# demo_V1_SMALL_SIZE.net
KiCad netlist of a schematic drawn in Altium Designer
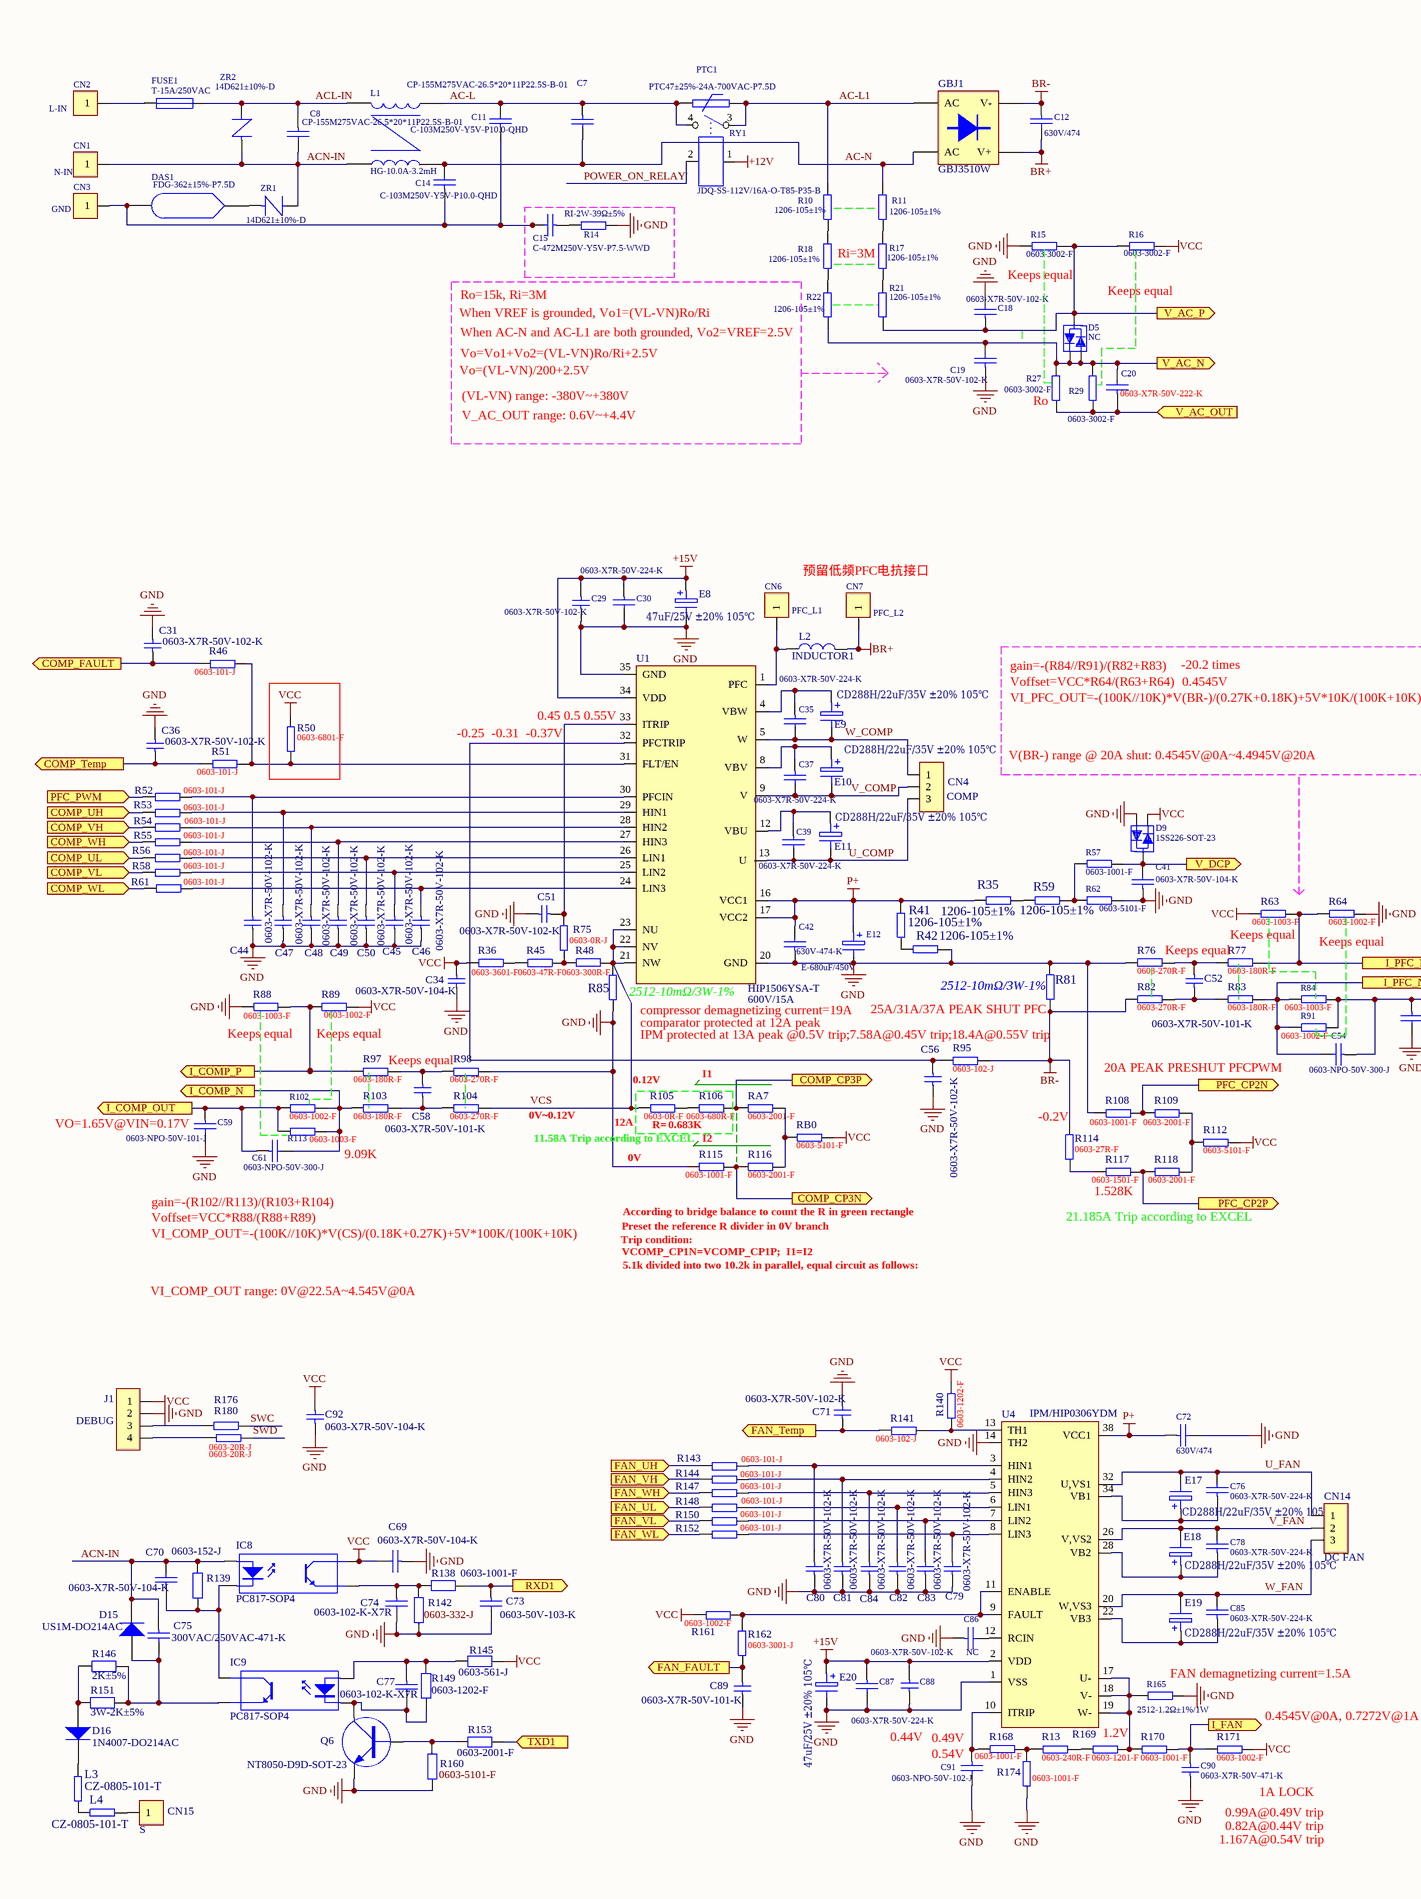
[diagram p0: demo_V1 SMALL SIZE.SchDoc, left]
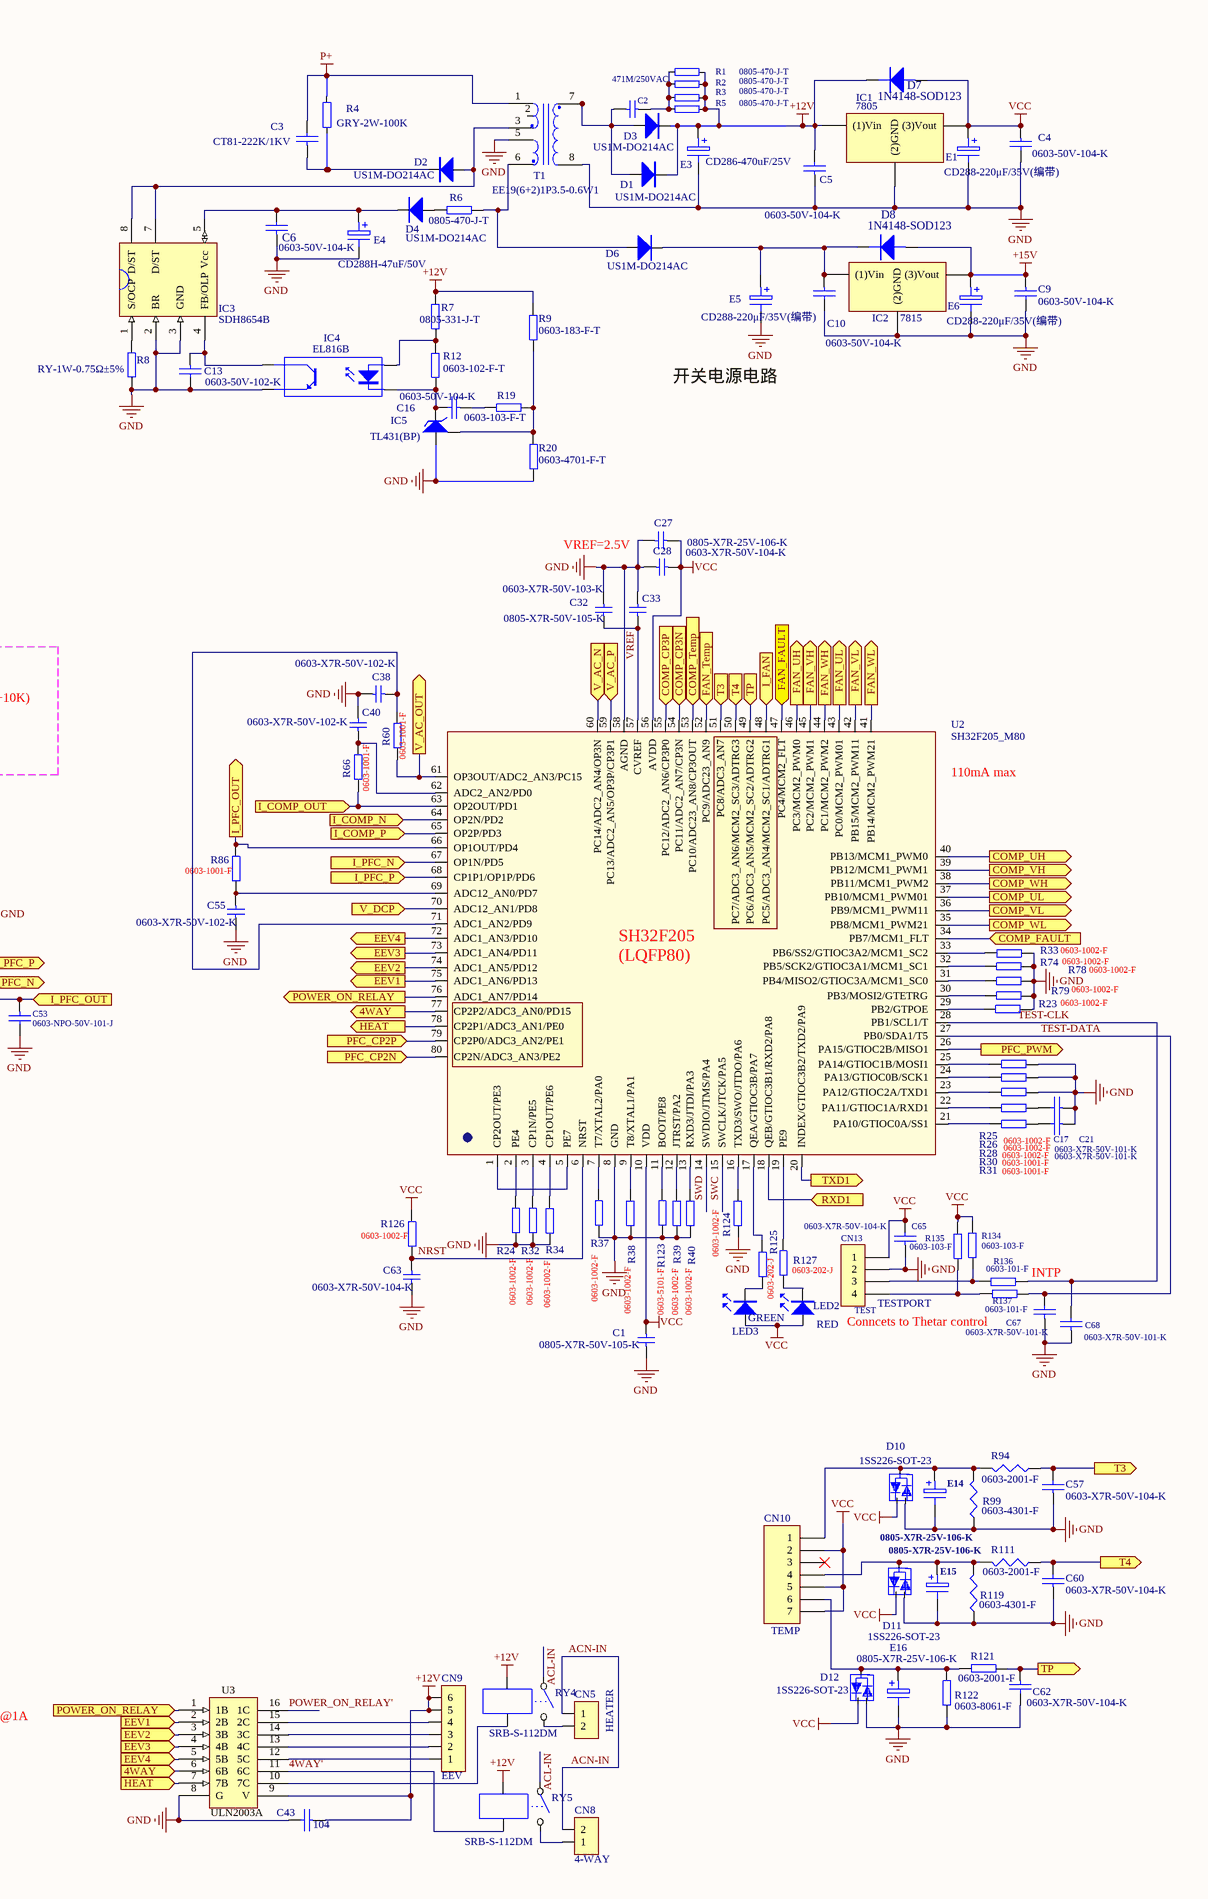
[diagram p1: demo_V1 SMALL SIZE.SchDoc, right]

(export (version "E")
  (design (tool "Eeschema 10.0.6"))
  (components
    (comp (ref "C1")
      (value "0805-X7R-50V-105-K")
      (footprint "R-SMT-SP-CAP/0805")
      (description "贴片电容")
      (libsource (lib "*") (part "C"))
    )
    (comp (ref "C2")
      (value "471M/250VAC")
      (footprint "S-C/5-AI")
      (description "Capacitor")
      (libsource (lib "") (part "C_1"))
    )
    (comp (ref "C3")
      (value "CT81-222K/1KV")
      (footprint "S-C/5-AI")
      (description "Capacitor")
      (libsource (lib "*") (part "CAP"))
    )
    (comp (ref "C4")
      (value "0603-50V-104-K")
      (footprint "R-SMT-SP-CAP/0603")
      (description "Capacitor")
      (libsource (lib "*") (part "CAP"))
    )
    (comp (ref "C5")
      (value "0603-50V-104-K")
      (footprint "R-SMT-SP-CAP/0603")
      (description "Capacitor")
      (libsource (lib "*") (part "CAP"))
    )
    (comp (ref "C6")
      (value "0603-50V-104-K")
      (footprint "R-SMT-SP-CAP/0603")
      (description "Capacitor")
      (libsource (lib "*") (part "CAP_V"))
    )
    (comp (ref "C7")
      (value "CP-155M275VAC-26.5*20*11P22.5S-B-01")
      (footprint "S-C/22.5")
      (description "Capacitor")
      (libsource (lib "*") (part "CAP"))
    )
    (comp (ref "C8")
      (value "CP-155M275VAC-26.5*20*11P22.5S-B-01")
      (footprint "S-C/22.5")
      (description "Capacitor")
      (libsource (lib "*") (part "CAP"))
    )
    (comp (ref "C9")
      (value "0603-50V-104-K")
      (footprint "R-SMT-SP-CAP/0603")
      (description "Capacitor")
      (libsource (lib "*") (part "CAP"))
    )
    (comp (ref "C10")
      (value "0603-50V-104-K")
      (footprint "R-SMT-SP-CAP/0603")
      (description "Capacitor")
      (libsource (lib "*") (part "CAP"))
    )
    (comp (ref "C11")
      (value "C-103M250V-Y5V-P10.0-QHD")
      (footprint "S-C/7.5+10/13X3-AI")
      (description "Capacitor")
      (libsource (lib "*") (part "CAP"))
    )
    (comp (ref "C12")
      (value "630V/474")
      (footprint "S-C/22.5/25X8.5")
      (description "Capacitor")
      (libsource (lib "*") (part "CAP"))
    )
    (comp (ref "C13")
      (value "0603-50V-102-K")
      (footprint "R-SMT-SP-CAP/0603")
      (description "Capacitor")
      (libsource (lib "*") (part "CAP"))
    )
    (comp (ref "C14")
      (value "C-103M250V-Y5V-P10.0-QHD")
      (footprint "S-C/7.5+10/13X3-AI")
      (description "Capacitor")
      (libsource (lib "*") (part "CAP"))
    )
    (comp (ref "C15")
      (value "C-472M250V-Y5V-P7.5-WWD")
      (footprint "S-C/7.5+10/13X3-AI")
      (description "Capacitor")
      (libsource (lib "*") (part "CAP"))
    )
    (comp (ref "C16")
      (value "0603-50V-104-K")
      (footprint "R-SMT-SP-CAP/0603")
      (description "Capacitor")
      (libsource (lib "*") (part "CAP"))
    )
    (comp (ref "C17")
      (value "0603-X7R-50V-101-K")
      (footprint "C/0603-SMT")
      (description "Capacitor")
      (libsource (lib "*") (part "CAP"))
    )
    (comp (ref "C18")
      (value "0603-X7R-50V-102-K")
      (footprint "R-SMT-SP-CAP/0603")
      (description "贴片电容")
      (libsource (lib "*") (part "CAP"))
    )
    (comp (ref "C19")
      (value "0603-X7R-50V-102-K")
      (footprint "R-SMT-SP-CAP/0603")
      (description "贴片电容")
      (libsource (lib "*") (part "CAP"))
    )
    (comp (ref "C20")
      (value "0603-X7R-50V-222-K")
      (footprint "R-SMT-SP-CAP/0603")
      (description "贴片电容")
      (libsource (lib "*") (part "CAP"))
    )
    (comp (ref "C21")
      (value "0603-X7R-50V-101-K")
      (footprint "C/0603-SMT")
      (description "Capacitor")
      (libsource (lib "*") (part "CAP"))
    )
    (comp (ref "C27")
      (value "0805-X7R-25V-106-K")
      (footprint "R-SMT-SP-CAP/0805")
      (description "贴片电容")
      (libsource (lib "*") (part "C"))
    )
    (comp (ref "C28")
      (value "0603-X7R-50V-104-K")
      (footprint "R-SMT-SP-CAP/0603")
      (description "贴片电容")
      (libsource (lib "*") (part "C"))
    )
    (comp (ref "C29")
      (value "0603-X7R-50V-102-K")
      (footprint "R-SMT-SP-CAP/0603")
      (description "贴片电容")
      (libsource (lib "") (part "C_1"))
    )
    (comp (ref "C30")
      (value "0603-X7R-50V-224-K")
      (footprint "R-SMT-SP-CAP/0603")
      (description "贴片电容")
      (libsource (lib "*") (part "CAP"))
    )
    (comp (ref "C31")
      (value "0603-X7R-50V-102-K")
      (footprint "R-SMT-SP-CAP/0603")
      (description "贴片电容")
      (libsource (lib "*") (part "C"))
    )
    (comp (ref "C32")
      (value "0805-X7R-50V-105-K")
      (footprint "R-SMT-SP-CAP/0805")
      (description "贴片电容")
      (libsource (lib "*") (part "C"))
    )
    (comp (ref "C33")
      (value "0603-X7R-50V-103-K")
      (footprint "R-SMT-SP-CAP/0603")
      (description "贴片电容")
      (libsource (lib "*") (part "C"))
    )
    (comp (ref "C34")
      (value "0603-X7R-50V-104-K")
      (footprint "R-SMT-SP-CAP/0603")
      (description "贴片电容")
      (libsource (lib "*") (part "C"))
    )
    (comp (ref "C35")
      (value "0603-X7R-50V-224-K")
      (footprint "R-SMT-SP-CAP/0603")
      (description "贴片电容")
      (libsource (lib "*") (part "CAP"))
    )
    (comp (ref "C36")
      (value "0603-X7R-50V-102-K")
      (footprint "R-SMT-SP-CAP/0603")
      (description "贴片电容")
      (libsource (lib "*") (part "C"))
    )
    (comp (ref "C37")
      (value "0603-X7R-50V-224-K")
      (footprint "R-SMT-SP-CAP/0603")
      (description "贴片电容")
      (libsource (lib "*") (part "CAP"))
    )
    (comp (ref "C38")
      (value "0603-X7R-50V-102-K")
      (footprint "R-SMT-SP-CAP/0603")
      (description "贴片电容")
      (libsource (lib "*") (part "C"))
    )
    (comp (ref "C39")
      (value "0603-X7R-50V-224-K")
      (footprint "R-SMT-SP-CAP/0603")
      (description "贴片电容")
      (libsource (lib "*") (part "CAP"))
    )
    (comp (ref "C40")
      (value "0603-X7R-50V-102-K")
      (footprint "R-SMT-SP-CAP/0603")
      (description "贴片电容")
      (libsource (lib "*") (part "C"))
    )
    (comp (ref "C41")
      (value "0603-X7R-50V-104-K")
      (footprint "R-SMT-SP-CAP/0603")
      (description "贴片电容")
      (libsource (lib "*") (part "CAP"))
    )
    (comp (ref "C42")
      (value "630V-474-K")
      (footprint "C/15/17/8.2")
      (description "MKP62电容-X2R-275VAC-474-K 17.5*18.5*7.5mm P=15mm CQC\\UL\\VDE认证 法拉")
      (libsource (lib "*") (part "CAP"))
    )
    (comp (ref "C43")
      (value "104")
      (footprint "C/0805")
      (description "Capacitor")
      (libsource (lib "") (part "CAP_3"))
    )
    (comp (ref "C44")
      (value "0603-X7R-50V-102-K")
      (footprint "R-SMT-SP-CAP/0603")
      (description "贴片电容")
      (libsource (lib "*") (part "C"))
    )
    (comp (ref "C45")
      (value "0603-X7R-50V-102-K")
      (footprint "R-SMT-SP-CAP/0603")
      (description "贴片电容")
      (libsource (lib "*") (part "C"))
    )
    (comp (ref "C46")
      (value "0603-X7R-50V-102-K")
      (footprint "R-SMT-SP-CAP/0603")
      (description "贴片电容")
      (libsource (lib "*") (part "C"))
    )
    (comp (ref "C47")
      (value "0603-X7R-50V-102-K")
      (footprint "R-SMT-SP-CAP/0603")
      (description "贴片电容")
      (libsource (lib "*") (part "C"))
    )
    (comp (ref "C48")
      (value "0603-X7R-50V-102-K")
      (footprint "R-SMT-SP-CAP/0603")
      (description "贴片电容")
      (libsource (lib "*") (part "C"))
    )
    (comp (ref "C49")
      (value "0603-X7R-50V-102-K")
      (footprint "R-SMT-SP-CAP/0603")
      (description "贴片电容")
      (libsource (lib "*") (part "C"))
    )
    (comp (ref "C50")
      (value "0603-X7R-50V-102-K")
      (footprint "R-SMT-SP-CAP/0603")
      (description "贴片电容")
      (libsource (lib "*") (part "C"))
    )
    (comp (ref "C51")
      (value "0603-X7R-50V-102-K")
      (footprint "R-SMT-SP-CAP/0603")
      (description "贴片电容")
      (libsource (lib "") (part "C_2"))
    )
    (comp (ref "C52")
      (value "0603-X7R-50V-101-K")
      (footprint "R-SMT-SP-CAP/0603")
      (description "贴片电容")
      (libsource (lib "*") (part "C"))
    )
    (comp (ref "C53")
      (value "0603-NPO-50V-101-J")
      (footprint "R-SMT-SP-CAP/0603")
      (description "贴片电容")
      (libsource (lib "*") (part "CAP"))
    )
    (comp (ref "C54")
      (value "0603-NPO-50V-300-J")
      (footprint "R-SMT-SP-CAP/0603")
      (description "贴片电容")
      (libsource (lib "*") (part "CAP"))
    )
    (comp (ref "C55")
      (value "0603-X7R-50V-102-K")
      (footprint "R-SMT-SP-CAP/0603")
      (description "贴片电容")
      (libsource (lib "*") (part "C"))
    )
    (comp (ref "C56")
      (value "0603-X7R-50V-102-K")
      (footprint "R-SMT-SP-CAP/0603")
      (description "贴片电容")
      (libsource (lib "*") (part "C"))
    )
    (comp (ref "C57")
      (value "0603-X7R-50V-104-K")
      (footprint "R-SMT-SP-CAP/0603")
      (description "贴片电容")
      (libsource (lib "") (part "CAP_2"))
    )
    (comp (ref "C58")
      (value "0603-X7R-50V-101-K")
      (footprint "R-SMT-SP-CAP/0603")
      (description "贴片电容")
      (libsource (lib "*") (part "C"))
    )
    (comp (ref "C59")
      (value "0603-NPO-50V-101-J")
      (footprint "R-SMT-SP-CAP/0603")
      (description "贴片电容")
      (libsource (lib "*") (part "CAP"))
    )
    (comp (ref "C60")
      (value "0603-X7R-50V-104-K")
      (footprint "R-SMT-SP-CAP/0603")
      (description "贴片电容")
      (libsource (lib "") (part "CAP_2"))
    )
    (comp (ref "C61")
      (value "0603-NPO-50V-300-J")
      (footprint "R-SMT-SP-CAP/0603")
      (description "贴片电容")
      (libsource (lib "*") (part "CAP"))
    )
    (comp (ref "C62")
      (value "0603-X7R-50V-104-K")
      (footprint "R-SMT-SP-CAP/0603")
      (description "贴片电容")
      (libsource (lib "*") (part "CAP"))
    )
    (comp (ref "C63")
      (value "0603-X7R-50V-104-K")
      (footprint "R-SMT-SP-CAP/0603")
      (description "贴片电容")
      (libsource (lib "*") (part "C"))
    )
    (comp (ref "C65")
      (value "0603-X7R-50V-104-K")
      (footprint "C/0603-SMT")
      (description "Capacitor")
      (libsource (lib "*") (part "CAP"))
    )
    (comp (ref "C67")
      (value "0603-X7R-50V-101-K")
      (footprint "C/0603-SMT")
      (description "Capacitor")
      (libsource (lib "*") (part "CAP"))
    )
    (comp (ref "C68")
      (value "0603-X7R-50V-101-K")
      (footprint "C/0603-SMT")
      (description "Capacitor")
      (libsource (lib "*") (part "CAP"))
    )
    (comp (ref "C69")
      (value "0603-X7R-50V-104-K")
      (footprint "R-SMT-SP-CAP/0603")
      (description "贴片电容")
      (libsource (lib "") (part "CAP_2"))
    )
    (comp (ref "C70")
      (value "0603-X7R-50V-104-K")
      (footprint "R-SMT-SP-CAP/0603")
      (description "贴片电容")
      (libsource (lib "显示板项目") (part "CAP"))
    )
    (comp (ref "C71")
      (value "0603-X7R-50V-102-K")
      (footprint "R-SMT-SP-CAP/0603")
      (description "贴片电容")
      (libsource (lib "*") (part "C"))
    )
    (comp (ref "C72")
      (value "630V/474")
      (footprint "C/15/17/8.2")
      (description "MKP62电容-X2R-275VAC-474-K 17.5*18.5*7.5mm P=15mm CQC\\UL\\VDE认证 法拉")
      (libsource (lib "*") (part "CAP"))
    )
    (comp (ref "C73")
      (value "0603-50V-103-K")
      (footprint "R-SMT-SP-CAP/0603")
      (description "贴片电容")
      (libsource (lib "") (part "CAP_1"))
    )
    (comp (ref "C74")
      (value "0603-102-K-X7R")
      (footprint "R-SMT-SP-CAP/0603")
      (description "贴片电容")
      (libsource (lib "") (part "CAP_1"))
    )
    (comp (ref "C75")
      (value "300VAC/250VAC-471-K")
      (footprint "S-C/7.5")
      (description "Y2电容R-300VAC/250VAC-471-K P=7.5mm 编带 TDK/村田")
      (libsource (lib "") (part "CAP_1"))
    )
    (comp (ref "C76")
      (value "0603-X7R-50V-224-K")
      (footprint "R-SMT-SP-CAP/0603")
      (description "贴片电容")
      (libsource (lib "*") (part "CAP"))
    )
    (comp (ref "C77")
      (value "0603-102-K-X7R")
      (footprint "R-SMT-SP-CAP/0603")
      (description "贴片电容")
      (libsource (lib "") (part "CAP_1"))
    )
    (comp (ref "C78")
      (value "0603-X7R-50V-224-K")
      (footprint "R-SMT-SP-CAP/0603")
      (description "贴片电容")
      (libsource (lib "*") (part "CAP"))
    )
    (comp (ref "C79")
      (value "0603-X7R-50V-102-K")
      (footprint "R-SMT-SP-CAP/0603")
      (description "贴片电容")
      (libsource (lib "*") (part "C"))
    )
    (comp (ref "C80")
      (value "0603-X7R-50V-102-K")
      (footprint "R-SMT-SP-CAP/0603")
      (description "贴片电容")
      (libsource (lib "*") (part "C"))
    )
    (comp (ref "C81")
      (value "0603-X7R-50V-102-K")
      (footprint "R-SMT-SP-CAP/0603")
      (description "贴片电容")
      (libsource (lib "*") (part "C"))
    )
    (comp (ref "C82")
      (value "0603-X7R-50V-102-K")
      (footprint "R-SMT-SP-CAP/0603")
      (description "贴片电容")
      (libsource (lib "*") (part "C"))
    )
    (comp (ref "C83")
      (value "0603-X7R-50V-102-K")
      (footprint "R-SMT-SP-CAP/0603")
      (description "贴片电容")
      (libsource (lib "*") (part "C"))
    )
    (comp (ref "C84")
      (value "0603-X7R-50V-102-K")
      (footprint "R-SMT-SP-CAP/0603")
      (description "贴片电容")
      (libsource (lib "*") (part "C"))
    )
    (comp (ref "C85")
      (value "0603-X7R-50V-224-K")
      (footprint "R-SMT-SP-CAP/0603")
      (description "贴片电容")
      (libsource (lib "*") (part "CAP"))
    )
    (comp (ref "C86")
      (value "NC")
      (footprint "R-SMT-SP-CAP/0603")
      (description "贴片电容")
      (libsource (lib "*") (part "CAP"))
    )
    (comp (ref "C87")
      (value "0603-X7R-50V-224-K")
      (footprint "R-SMT-SP-CAP/0603")
      (description "贴片电容")
      (libsource (lib "*") (part "CAP"))
    )
    (comp (ref "C88")
      (value "0603-X7R-50V-102-K")
      (footprint "R-SMT-SP-CAP/0603")
      (description "贴片电容")
      (libsource (lib "") (part "C_1"))
    )
    (comp (ref "C89")
      (value "0603-X7R-50V-101-K")
      (footprint "R-SMT-SP-CAP/0603")
      (description "贴片电容")
      (libsource (lib "*") (part "C"))
    )
    (comp (ref "C90")
      (value "0603-X7R-50V-471-K")
      (footprint "R-SMT-SP-CAP/0603")
      (description "贴片电容")
      (libsource (lib "") (part "C_1"))
    )
    (comp (ref "C91")
      (value "0603-NPO-50V-102-J")
      (footprint "R-SMT-SP-CAP/0603")
      (description "贴片电容")
      (libsource (lib "*") (part "CAP"))
    )
    (comp (ref "C92")
      (value "0603-X7R-50V-104-K")
      (footprint "R-SMT-SP-CAP/0603")
      (description "贴片电容")
      (libsource (lib "*") (part "C"))
    )
    (comp (ref "CN1")
      (value "N-IN")
      (footprint "0-P")
      (description "Connector")
      (libsource (lib "*") (part "CON1"))
    )
    (comp (ref "CN2")
      (value "L-IN")
      (footprint "0-P")
      (description "Connector")
      (libsource (lib "*") (part "CON1"))
    )
    (comp (ref "CN3")
      (value "GND")
      (footprint "S-P/0/2.5/4.5")
      (description "Connector")
      (libsource (lib "*") (part "CON1"))
    )
    (comp (ref "CN4")
      (value "COMP")
      (footprint "R-SC-CN/FD/4/4/20/8.6(VH-5K2,4)")
      (description "Connector")
      (libsource (lib "原理图库SCHLIB") (part "CON3"))
    )
    (comp (ref "CN5")
      (value "HEATER")
      (footprint "S-CN/7.92/2/L")
      (description "插座")
      (libsource (lib "原理图SCHLIB(2009.06.30更新)") (part "CON2"))
    )
    (comp (ref "CN6")
      (value "PFC_L1")
      (footprint "R-SC-P/TP2.5SING(14AWG)")
      (description "Connector")
      (libsource (lib "") (part "CON1_1"))
    )
    (comp (ref "CN7")
      (value "PFC_L2")
      (footprint "R-SC-P/TP2.5SING(14AWG)")
      (description "Connector")
      (libsource (lib "") (part "CON1_1"))
    )
    (comp (ref "CN8")
      (value "4-WAY")
      (footprint "S-CN/7.92/2/L")
      (description "插座")
      (libsource (lib "") (part "CON2_1"))
    )
    (comp (ref "CN9")
      (value "EEV")
      (footprint "S-CN/2.54/6/L")
      (description "Connector")
      (libsource (lib "Sch98") (part "CON6"))
    )
    (comp (ref "CN10")
      (value "TEMP")
      (footprint "R-SC-CN/2.5/7/11.5/4.5/JS")
      (description "温度传感器线组")
      (fields (field (name "PUBLISHER") "Altium Limited"))
      (libsource (lib "Miscellaneous Connectors") (part "Header 7"))
    )
    (comp (ref "CN13")
      (value "TEST")
      (footprint "S-CN/2.54/4/L")
      (description "Connector")
      (libsource (lib "*") (part "CON4"))
    )
    (comp (ref "CN14")
      (value "DC FAN")
      (footprint "R-SC-CN/FD/4/4/20/8.6(VH-5K2,4)")
      (description "Connector")
      (libsource (lib "原理图库SCHLIB") (part "CON3"))
    )
    (comp (ref "CN15")
      (value "S")
      (footprint "0-P")
      (description "Connector")
      (libsource (lib "原理图库SCHLIB") (part "CON1"))
    )
    (comp (ref "D1")
      (value "US1M-DO214AC")
      (footprint "D/SUF4007")
      (description "Diode")
      (libsource (lib "*") (part "DIODE"))
    )
    (comp (ref "D2")
      (value "US1M-DO214AC")
      (footprint "D/SUF4007")
      (description "Diode")
      (libsource (lib "*") (part "DIODE"))
    )
    (comp (ref "D3")
      (value "US1M-DO214AC")
      (footprint "D/SUF4007")
      (description "Diode")
      (libsource (lib "*") (part "DIODE"))
    )
    (comp (ref "D4")
      (value "US1M-DO214AC")
      (footprint "D/SUF4007")
      (description "Diode")
      (libsource (lib "*") (part "DIODE"))
    )
    (comp (ref "D5") (value "NC") (footprint "D/TYPE/1SS226-SMT") (libsource (lib "*") (part "0-D/1SS226")))
    (comp (ref "D6")
      (value "US1M-DO214AC")
      (footprint "D/SUF4007")
      (description "Diode")
      (libsource (lib "*") (part "DIODE"))
    )
    (comp (ref "D7")
      (value "1N4148-SOD123")
      (footprint "D/SOD123-SMT")
      (description "Diode")
      (libsource (lib "*") (part "D-HER107"))
    )
    (comp (ref "D8")
      (value "1N4148-SOD123")
      (footprint "D/SOD123-SMT")
      (description "Diode")
      (libsource (lib "*") (part "D-HER107"))
    )
    (comp (ref "D9")
      (value "1SS226-SOT-23")
      (footprint "D/TYPE/1SS226-SMT")
      (libsource (lib "*") (part "0-D/1SS226"))
    )
    (comp (ref "D10")
      (value "1SS226-SOT-23")
      (footprint "D/TYPE/1SS226-SMT")
      (description "双向二极管")
      (libsource (lib "SCHLIB") (part "1SS226"))
    )
    (comp (ref "D11")
      (value "1SS226-SOT-23")
      (footprint "D/TYPE/1SS226-SMT")
      (description "双向二极管")
      (libsource (lib "SCHLIB") (part "1SS226"))
    )
    (comp (ref "D12")
      (value "1SS226-SOT-23")
      (footprint "D/TYPE/1SS226-SMT")
      (description "双向二极管")
      (libsource (lib "SCHLIB") (part "1SS226"))
    )
    (comp (ref "D15")
      (value "US1M-DO214AC")
      (footprint "D/DO214AC-SMT")
      (description "Default Diode")
      (fields (field (name "PUBLISHER") "Altium Limited"))
      (libsource (lib "GI10-I32") (part "Diode"))
    )
    (comp (ref "D16")
      (value "1N4007-DO214AC")
      (footprint "D/DO214AC-SMT")
      (description "Default Diode")
      (fields (field (name "PUBLISHER") "Altium Limited"))
      (libsource (lib "") (part "Diode_1"))
    )
    (comp (ref "DAS1")
      (value "FDG-362±15%-P7.5D")
      (footprint "S-DSA/7.5/0.9-AI")
      (libsource (lib "*") (part "ASS"))
    )
    (comp (ref "E1")
      (value "CD288-220μF/35V(编带)")
      (footprint "R-SC-CAP-EC/5/8")
      (description "Electrolytic Capacitor")
      (libsource (lib "") (part "ELECTRO1_1"))
    )
    (comp (ref "E3")
      (value "CD286-470uF/25V")
      (footprint "E/5/11-AI")
      (description "Electrolytic Capacitor")
      (libsource (lib "") (part "ELECTRO1_1"))
    )
    (comp (ref "E4")
      (value "CD288H-47uF/50V")
      (footprint "E/2.54/6.5-AI")
      (description "Electrolytic Capacitor")
      (libsource (lib "") (part "ELECTRO1_1"))
    )
    (comp (ref "E5")
      (value "CD288-220μF/35V(编带)")
      (footprint "R-SC-CAP-EC/5/8")
      (description "Electrolytic Capacitor")
      (libsource (lib "") (part "ELECTRO1_1"))
    )
    (comp (ref "E6")
      (value "CD288-220μF/35V(编带)")
      (footprint "R-SC-CAP-EC/5/8")
      (description "Electrolytic Capacitor")
      (libsource (lib "") (part "ELECTRO1_1"))
    )
    (comp (ref "E8")
      (value "47uF/25V ±20% 105℃")
      (footprint "E/2.5/5/E1@")
      (description "贴片电解电容R-47uF/35V ±20% 105℃ 6.3*5.4mm 利明")
      (libsource (lib "*") (part "ELECTRO1"))
    )
    (comp (ref "E9")
      (value "CD288H/22uF/35V ±20% 105℃")
      (footprint "E/2.5/5/E1@")
      (description "贴片电解电容R-47uF/35V ±20% 105℃ 6.3*5.4mm 利明")
      (libsource (lib "*") (part "ELECTRO1"))
    )
    (comp (ref "E10")
      (value "CD288H/22uF/35V ±20% 105℃")
      (footprint "E/2.5/5/E1@")
      (description "贴片电解电容R-47uF/35V ±20% 105℃ 6.3*5.4mm 利明")
      (libsource (lib "*") (part "ELECTRO1"))
    )
    (comp (ref "E11")
      (value "CD288H/22uF/35V ±20% 105℃")
      (footprint "E/2.5/5/E1@")
      (description "贴片电解电容R-47uF/35V ±20% 105℃ 6.3*5.4mm 利明")
      (libsource (lib "*") (part "ELECTRO1"))
    )
    (comp (ref "E12")
      (value "E-680uF/450V")
      (footprint "S-E/10/36L-1")
      (description "Electrolytic Capacitor")
      (libsource (lib "") (part "ELECTRO1_2"))
    )
    (comp (ref "E14")
      (value "0805-X7R-25V-106-K")
      (footprint "R-SMT-SP-CAP/0805")
      (description "电解电容R-GR 47μF/25V ±20% 105℃ 5*11mm P=2.5mm")
      (libsource (lib "*") (part "KFR70B.S01_47uf_16"))
    )
    (comp (ref "E15")
      (value "0805-X7R-25V-106-K")
      (footprint "R-SMT-SP-CAP/0805")
      (description "电解电容R-GR 47μF/25V ±20% 105℃ 5*11mm P=2.5mm")
      (libsource (lib "*") (part "KFR70B.S01_47uf_16"))
    )
    (comp (ref "E16")
      (value "0805-X7R-25V-106-K")
      (footprint "R-SMT-SP-CAP/0805")
      (description "电解电容R-GR 47μF/25V ±20% 105℃ 5*11mm P=2.5mm")
      (libsource (lib "") (part "ELECTRO1_1"))
    )
    (comp (ref "E17")
      (value "CD288H/22uF/35V ±20% 105℃")
      (footprint "E/2.5/5/E1@")
      (description "贴片电解电容R-47uF/35V ±20% 105℃ 6.3*5.4mm 利明")
      (libsource (lib "*") (part "ELECTRO1"))
    )
    (comp (ref "E18")
      (value "CD288H/22uF/35V ±20% 105℃")
      (footprint "E/2.5/5/E1@")
      (description "贴片电解电容R-47uF/35V ±20% 105℃ 6.3*5.4mm 利明")
      (libsource (lib "*") (part "ELECTRO1"))
    )
    (comp (ref "E19")
      (value "CD288H/22uF/35V ±20% 105℃")
      (footprint "E/2.5/5/E1@")
      (description "贴片电解电容R-47uF/35V ±20% 105℃ 6.3*5.4mm 利明")
      (libsource (lib "*") (part "ELECTRO1"))
    )
    (comp (ref "E20")
      (value "47uF/25V ±20% 105℃")
      (footprint "E/2.5/5/E1@")
      (description "贴片电解电容R-47uF/35V ±20% 105℃ 6.3*5.4mm 利明")
      (libsource (lib "*") (part "ELECTRO1"))
    )
    (comp (ref "FUSE1") (value "T-15A/250VAC") (footprint "S-FU/2/32/7") (libsource (lib "*") (part "FUSE")))
    (comp (ref "GBJ1")
      (value "GBJ3510W")
      (footprint "R-SC-DIO-DB/AC-DC1(WS)")
      (description "整流桥堆")
      (libsource (lib "原理图库NEW") (part "BRIDGE1"))
    )
    (comp (ref "IC1")
      (value "7805")
      (footprint "R-SMT-SP-IC/78XX")
      (description "VOLTREG")
      (libsource (lib "midea_gaojs") (part "VOLTREG"))
    )
    (comp (ref "IC2")
      (value "7815")
      (footprint "R-SMT-SP-IC/78XX")
      (description "VOLTREG")
      (libsource (lib "midea_gaojs") (part "VOLTREG"))
    )
    (comp (ref "IC3") (value "SDH8654B") (footprint "IC/DIP/8") (libsource (lib "*") (part "IC/STR-A6069H")))
    (comp (ref "IC4")
      (value "EL816B")
      (footprint "IC/DIP/4/1")
      (description "Optoisolator")
      (libsource (lib "原理图SCHLIB(2009.02.18更新)") (part "OPTOISO1"))
    )
    (comp (ref "IC5")
      (value "TL431(BP)")
      (footprint "Q/SOT23-SMT-431")
      (libsource (lib "*") (part "IC/TL431"))
    )
    (comp (ref "IC8")
      (value "PC817-SOP4")
      (footprint "R-SMT-SP-IC/SOP/2.54/4")
      (description "Optoisolator")
      (libsource (lib "原理图库SCHLIB") (part "OPTOISO1"))
    )
    (comp (ref "IC9")
      (value "PC817-SOP4")
      (footprint "R-SMT-SP-IC/SOP/2.54/4")
      (description "Optoisolator")
      (libsource (lib "原理图库SCHLIB") (part "OPTOISO1"))
    )
    (comp (ref "J1") (value "DEBUG") (footprint "SIP4") (libsource (lib "Sch98") (part "CON4")))
    (comp (ref "L1")
      (value "HG-10.0A-3.2mH")
      (footprint "0-S-L/4/50/35/")
      (libsource (lib "*") (part "PLT1"))
    )
    (comp (ref "L2")
      (value "INDUCTOR1")
      (footprint "0-L/10A-400uH")
      (description "INDUCTOR")
      (libsource (lib "原理图库SCHLIB") (part "INDUCTOR1"))
    )
    (comp (ref "L3")
      (value "CZ-0805-101-T")
      (footprint "R/0805-SMT")
      (description "贴片磁珠")
      (libsource (lib "*") (part "RES"))
    )
    (comp (ref "L4")
      (value "CZ-0805-101-T")
      (footprint "R/0805-SMT")
      (description "贴片磁珠")
      (libsource (lib "*") (part "RES"))
    )
    (comp (ref "LED2")
      (value "RED")
      (footprint "R-SMT-SP-LED/0603")
      (libsource (lib "原理图库SCHLIB") (part "LED"))
    )
    (comp (ref "LED3")
      (value "GREEN")
      (footprint "R-SMT-SP-LED/0603")
      (libsource (lib "原理图库SCHLIB") (part "LED"))
    )
    (comp (ref "PTC1")
      (value "PTC47±25%-24A-700VAC-P7.5D")
      (footprint "S-PTC/03")
      (libsource (lib "*") (part "THERMAL RESISTOR"))
    )
    (comp (ref "Q6")
      (value "NT8050-D9D-SOT-23")
      (footprint "Q/SOT23-SMT")
      (description "贴片三极管")
      (libsource (lib "*") (part "NPN"))
    )
    (comp (ref "R1")
      (value "0805-470-J-T")
      (footprint "R/0805")
      (description "Resistance")
      (libsource (lib "*") (part "R"))
    )
    (comp (ref "R2")
      (value "0805-470-J-T")
      (footprint "R/0805")
      (description "Resistance")
      (libsource (lib "*") (part "R"))
    )
    (comp (ref "R3")
      (value "0805-470-J-T")
      (footprint "R/0805")
      (description "Resistance")
      (libsource (lib "*") (part "R"))
    )
    (comp (ref "R4")
      (value "GRY-2W-100K")
      (footprint "S-R/5/2W/R1-AI")
      (description "Resistance")
      (libsource (lib "*") (part "R"))
    )
    (comp (ref "R5")
      (value "0805-470-J-T")
      (footprint "R/0805")
      (description "Resistance")
      (libsource (lib "*") (part "R"))
    )
    (comp (ref "R6") (value "0805-470-J-T") (footprint "R/0805") (libsource (lib "*") (part "RES")))
    (comp (ref "R7") (value "0805-331-J-T") (footprint "R/0805") (libsource (lib "*") (part "RES")))
    (comp (ref "R8") (value "RY-1W-0.75Ω±5%") (footprint "S-R/5/1W/R1-AI") (libsource (lib "*") (part "RES")))
    (comp (ref "R9")
      (value "0603-183-F-T")
      (footprint "R-SMT-SP-RES/0603")
      (libsource (lib "*") (part "RES"))
    )
    (comp (ref "R10")
      (value "1206-105±1%")
      (footprint "R/1206")
      (description "贴片电阻")
      (libsource (lib "") (part "RES_1"))
    )
    (comp (ref "R11")
      (value "1206-105±1%")
      (footprint "R/1206")
      (description "贴片电阻")
      (libsource (lib "") (part "RES_1"))
    )
    (comp (ref "R12")
      (value "0603-102-F-T")
      (footprint "R-SMT-SP-RES/0603")
      (libsource (lib "*") (part "RES"))
    )
    (comp (ref "R13")
      (value "0603-240R-F")
      (footprint "R-SMT-SP-RES/0603")
      (description "贴片电阻")
      (libsource (lib "*") (part "RES5"))
    )
    (comp (ref "R14") (value "RI-2W-39Ω±5%") (footprint "S-R/5/1W/R1-AI") (libsource (lib "*") (part "RES")))
    (comp (ref "R15")
      (value "0603-3002-F")
      (footprint "R-SMT-SP-RES/0603")
      (description "贴片电阻")
      (libsource (lib "*") (part "RES5"))
    )
    (comp (ref "R16")
      (value "0603-3002-F")
      (footprint "R-SMT-SP-RES/0603")
      (description "贴片电阻")
      (libsource (lib "*") (part "RES5"))
    )
    (comp (ref "R17")
      (value "1206-105±1%")
      (footprint "R/1206")
      (description "贴片电阻")
      (libsource (lib "") (part "RES_1"))
    )
    (comp (ref "R18")
      (value "1206-105±1%")
      (footprint "R/1206")
      (description "贴片电阻")
      (libsource (lib "") (part "RES_1"))
    )
    (comp (ref "R19")
      (value "0603-103-F-T")
      (footprint "R-SMT-SP-RES/0603")
      (libsource (lib "*") (part "RES"))
    )
    (comp (ref "R20")
      (value "0603-4701-F-T")
      (footprint "R-SMT-SP-RES/0603")
      (libsource (lib "*") (part "RES"))
    )
    (comp (ref "R21")
      (value "1206-105±1%")
      (footprint "R/1206")
      (description "贴片电阻")
      (libsource (lib "") (part "RES_1"))
    )
    (comp (ref "R22")
      (value "1206-105±1%")
      (footprint "R/1206")
      (description "贴片电阻")
      (libsource (lib "") (part "RES_1"))
    )
    (comp (ref "R23")
      (value "0603-1002-F")
      (footprint "R-SMT-SP-RES/0603")
      (description "贴片电阻")
      (libsource (lib "*") (part "RES5"))
    )
    (comp (ref "R24")
      (value "0603-1002-F")
      (footprint "R-SMT-SP-RES/0603")
      (description "贴片电阻")
      (libsource (lib "*") (part "RES5"))
    )
    (comp (ref "R25")
      (value "0603-1002-F")
      (footprint "R-SMT-SP-RES/0603")
      (description "贴片电阻")
      (libsource (lib "*") (part "RES5"))
    )
    (comp (ref "R26")
      (value "0603-1002-F")
      (footprint "R-SMT-SP-RES/0603")
      (description "贴片电阻")
      (libsource (lib "*") (part "RES5"))
    )
    (comp (ref "R27")
      (value "0603-3002-F")
      (footprint "R-SMT-SP-RES/0603")
      (description "贴片电阻")
      (libsource (lib "*") (part "RES5"))
    )
    (comp (ref "R28")
      (value "0603-1002-F")
      (footprint "R-SMT-SP-RES/0603")
      (description "贴片电阻")
      (libsource (lib "*") (part "RES5"))
    )
    (comp (ref "R29")
      (value "0603-3002-F")
      (footprint "R-SMT-SP-RES/0603")
      (description "贴片电阻")
      (libsource (lib "*") (part "RES5"))
    )
    (comp (ref "R30")
      (value "0603-1001-F")
      (footprint "R-SMT-SP-RES/0603")
      (description "贴片电阻")
      (libsource (lib "*") (part "RES5"))
    )
    (comp (ref "R31")
      (value "0603-1001-F")
      (footprint "R-SMT-SP-RES/0603")
      (description "贴片电阻")
      (libsource (lib "*") (part "RES5"))
    )
    (comp (ref "R32")
      (value "0603-1002-F")
      (footprint "R-SMT-SP-RES/0603")
      (description "贴片电阻")
      (libsource (lib "*") (part "RES5"))
    )
    (comp (ref "R33")
      (value "0603-1002-F")
      (footprint "R-SMT-SP-RES/0603")
      (description "贴片电阻")
      (libsource (lib "*") (part "RES5"))
    )
    (comp (ref "R34")
      (value "0603-1002-F")
      (footprint "R-SMT-SP-RES/0603")
      (description "贴片电阻")
      (libsource (lib "*") (part "RES5"))
    )
    (comp (ref "R35")
      (value "1206-105±1%")
      (footprint "R/1206-SMT")
      (description "贴片电阻")
      (libsource (lib "*") (part "RES"))
    )
    (comp (ref "R36")
      (value "0603-3601-F")
      (footprint "R-SMT-SP-RES/0603")
      (description "贴片电阻")
      (libsource (lib "*") (part "RES5"))
    )
    (comp (ref "R37")
      (value "0603-1002-F")
      (footprint "R-SMT-SP-RES/0603")
      (description "贴片电阻")
      (libsource (lib "*") (part "RES5"))
    )
    (comp (ref "R38")
      (value "0603-1002-F")
      (footprint "R-SMT-SP-RES/0603")
      (description "贴片电阻")
      (libsource (lib "*") (part "RES5"))
    )
    (comp (ref "R39")
      (value "0603-1002-F")
      (footprint "R-SMT-SP-RES/0603")
      (description "贴片电阻")
      (libsource (lib "*") (part "RES5"))
    )
    (comp (ref "R40")
      (value "0603-1002-F")
      (footprint "R-SMT-SP-RES/0603")
      (description "贴片电阻")
      (libsource (lib "*") (part "RES5"))
    )
    (comp (ref "R41")
      (value "1206-105±1%")
      (footprint "R/1206-SMT")
      (description "贴片电阻")
      (libsource (lib "*") (part "RES"))
    )
    (comp (ref "R42")
      (value "1206-105±1%")
      (footprint "R/1206-SMT")
      (description "贴片电阻")
      (libsource (lib "*") (part "RES"))
    )
    (comp (ref "R45")
      (value "0603-47R-F")
      (footprint "R-SMT-SP-RES/0603")
      (description "贴片电阻")
      (libsource (lib "*") (part "RES5"))
    )
    (comp (ref "R46")
      (value "0603-101-J")
      (footprint "R-SMT-SP-RES/0603")
      (description "贴片电阻")
      (libsource (lib "*") (part "RES"))
    )
    (comp (ref "R48")
      (value "0603-300R-F")
      (footprint "R-SMT-SP-RES/0603")
      (description "贴片电阻")
      (libsource (lib "*") (part "RES5"))
    )
    (comp (ref "R50")
      (value "0603-6801-F")
      (footprint "R-SMT-SP-RES/0603")
      (description "贴片电阻")
      (libsource (lib "*") (part "RES5"))
    )
    (comp (ref "R51")
      (value "0603-101-J")
      (footprint "R-SMT-SP-RES/0603")
      (description "贴片电阻")
      (libsource (lib "*") (part "RES"))
    )
    (comp (ref "R52")
      (value "0603-101-J")
      (footprint "R-SMT-SP-RES/0603")
      (description "贴片电阻")
      (libsource (lib "*") (part "RES"))
    )
    (comp (ref "R53")
      (value "0603-101-J")
      (footprint "R-SMT-SP-RES/0603")
      (description "贴片电阻")
      (libsource (lib "*") (part "RES"))
    )
    (comp (ref "R54")
      (value "0603-101-J")
      (footprint "R-SMT-SP-RES/0603")
      (description "贴片电阻")
      (libsource (lib "*") (part "RES"))
    )
    (comp (ref "R55")
      (value "0603-101-J")
      (footprint "R-SMT-SP-RES/0603")
      (description "贴片电阻")
      (libsource (lib "*") (part "RES"))
    )
    (comp (ref "R56")
      (value "0603-101-J")
      (footprint "R-SMT-SP-RES/0603")
      (description "贴片电阻")
      (libsource (lib "*") (part "RES"))
    )
    (comp (ref "R57")
      (value "0603-1001-F")
      (footprint "R-SMT-SP-RES/0603")
      (description "贴片电阻")
      (libsource (lib "*") (part "RES"))
    )
    (comp (ref "R58")
      (value "0603-101-J")
      (footprint "R-SMT-SP-RES/0603")
      (description "贴片电阻")
      (libsource (lib "*") (part "RES"))
    )
    (comp (ref "R59")
      (value "1206-105±1%")
      (footprint "R/1206-SMT")
      (description "贴片电阻")
      (libsource (lib "*") (part "RES"))
    )
    (comp (ref "R60")
      (value "0603-1001-F")
      (footprint "R-SMT-SP-RES/0603")
      (description "贴片电阻")
      (libsource (lib "*") (part "RES5"))
    )
    (comp (ref "R61")
      (value "0603-101-J")
      (footprint "R-SMT-SP-RES/0603")
      (description "贴片电阻")
      (libsource (lib "*") (part "RES"))
    )
    (comp (ref "R62")
      (value "0603-5101-F")
      (footprint "R-SMT-SP-RES/0603")
      (description "贴片电阻")
      (libsource (lib "") (part "RES_2"))
    )
    (comp (ref "R63")
      (value "0603-1003-F")
      (footprint "R-SMT-SP-RES/0603")
      (description "贴片电阻")
      (libsource (lib "*") (part "RES"))
    )
    (comp (ref "R64")
      (value "0603-1002-F")
      (footprint "R-SMT-SP-RES/0603")
      (description "贴片电阻")
      (libsource (lib "*") (part "RES"))
    )
    (comp (ref "R66")
      (value "0603-1001-F")
      (footprint "R-SMT-SP-RES/0603")
      (description "贴片电阻")
      (libsource (lib "*") (part "RES5"))
    )
    (comp (ref "R74")
      (value "0603-1002-F")
      (footprint "R-SMT-SP-RES/0603")
      (description "贴片电阻")
      (libsource (lib "*") (part "RES5"))
    )
    (comp (ref "R75")
      (value "0603-0R-J")
      (footprint "R-SMT-SP-RES/0603")
      (description "贴片电阻")
      (libsource (lib "") (part "RES_2"))
    )
    (comp (ref "R76")
      (value "0603-270R-F")
      (footprint "R-SMT-SP-RES/0603")
      (description "贴片电阻")
      (libsource (lib "*") (part "RES"))
    )
    (comp (ref "R77")
      (value "0603-180R-F")
      (footprint "R-SMT-SP-RES/0603")
      (description "贴片电阻")
      (libsource (lib "*") (part "RES"))
    )
    (comp (ref "R78")
      (value "0603-1002-F")
      (footprint "R-SMT-SP-RES/0603")
      (description "贴片电阻")
      (libsource (lib "*") (part "RES5"))
    )
    (comp (ref "R79")
      (value "0603-1002-F")
      (footprint "R-SMT-SP-RES/0603")
      (description "贴片电阻")
      (libsource (lib "*") (part "RES5"))
    )
    (comp (ref "R81") (value "2512-10mΩ/3W-1%") (footprint "R/2512-SMT") (libsource (lib "*") (part "RES")))
    (comp (ref "R82")
      (value "0603-270R-F")
      (footprint "R-SMT-SP-RES/0603")
      (description "贴片电阻")
      (libsource (lib "*") (part "RES"))
    )
    (comp (ref "R83")
      (value "0603-180R-F")
      (footprint "R-SMT-SP-RES/0603")
      (description "贴片电阻")
      (libsource (lib "*") (part "RES"))
    )
    (comp (ref "R84")
      (value "0603-1003-F")
      (footprint "R-SMT-SP-RES/0603")
      (description "贴片电阻")
      (libsource (lib "*") (part "RES"))
    )
    (comp (ref "R85") (value "2512-10mΩ/3W-1%") (footprint "R/2512-SMT") (libsource (lib "*") (part "RES")))
    (comp (ref "R86")
      (value "0603-1001-F")
      (footprint "R-SMT-SP-RES/0603")
      (description "贴片电阻")
      (libsource (lib "*") (part "RES5"))
    )
    (comp (ref "R88")
      (value "0603-1003-F")
      (footprint "R-SMT-SP-RES/0603")
      (description "贴片电阻")
      (libsource (lib "*") (part "RES"))
    )
    (comp (ref "R89")
      (value "0603-1002-F")
      (footprint "R-SMT-SP-RES/0603")
      (description "贴片电阻")
      (libsource (lib "*") (part "RES"))
    )
    (comp (ref "R91")
      (value "0603-1002-F")
      (footprint "R-SMT-SP-RES/0603")
      (description "贴片电阻")
      (libsource (lib "*") (part "RES"))
    )
    (comp (ref "R94")
      (value "0603-2001-F")
      (footprint "R-SMT-SP-RES/0603")
      (description "贴片电阻")
      (libsource (lib "*") (part "RES1"))
    )
    (comp (ref "R95")
      (value "0603-102-J")
      (footprint "R-SMT-SP-RES/0603")
      (description "贴片电阻")
      (libsource (lib "*") (part "RES"))
    )
    (comp (ref "R97")
      (value "0603-180R-F")
      (footprint "R-SMT-SP-RES/0603")
      (description "贴片电阻")
      (libsource (lib "*") (part "RES"))
    )
    (comp (ref "R98")
      (value "0603-270R-F")
      (footprint "R-SMT-SP-RES/0603")
      (description "贴片电阻")
      (libsource (lib "*") (part "RES"))
    )
    (comp (ref "R99")
      (value "0603-4301-F")
      (footprint "R-SMT-SP-RES/0603")
      (description "贴片电阻")
      (libsource (lib "*") (part "RES1"))
    )
    (comp (ref "R102")
      (value "0603-1002-F")
      (footprint "R-SMT-SP-RES/0603")
      (description "贴片电阻")
      (libsource (lib "*") (part "RES"))
    )
    (comp (ref "R103")
      (value "0603-180R-F")
      (footprint "R-SMT-SP-RES/0603")
      (description "贴片电阻")
      (libsource (lib "*") (part "RES"))
    )
    (comp (ref "R104")
      (value "0603-270R-F")
      (footprint "R-SMT-SP-RES/0603")
      (description "贴片电阻")
      (libsource (lib "*") (part "RES"))
    )
    (comp (ref "R105")
      (value "0603-0R-F")
      (footprint "R-SMT-SP-RES/0603")
      (description "贴片电阻")
      (libsource (lib "*") (part "RES"))
    )
    (comp (ref "R106")
      (value "0603-680R-F")
      (footprint "R-SMT-SP-RES/0603")
      (description "贴片电阻")
      (libsource (lib "*") (part "RES"))
    )
    (comp (ref "R108")
      (value "0603-1001-F")
      (footprint "R-SMT-SP-RES/0603")
      (description "贴片电阻")
      (libsource (lib "*") (part "RES"))
    )
    (comp (ref "R109")
      (value "0603-2001-F")
      (footprint "R-SMT-SP-RES/0603")
      (description "贴片电阻")
      (libsource (lib "*") (part "RES"))
    )
    (comp (ref "R111")
      (value "0603-2001-F")
      (footprint "R-SMT-SP-RES/0603")
      (description "贴片电阻")
      (libsource (lib "*") (part "RES1"))
    )
    (comp (ref "R112")
      (value "0603-5101-F")
      (footprint "R-SMT-SP-RES/0603")
      (description "贴片电阻")
      (libsource (lib "*") (part "RES"))
    )
    (comp (ref "R113")
      (value "0603-1003-F")
      (footprint "R-SMT-SP-RES/0603")
      (description "贴片电阻")
      (libsource (lib "*") (part "RES"))
    )
    (comp (ref "R114")
      (value "0603-27R-F")
      (footprint "R-SMT-SP-RES/0603")
      (description "贴片电阻")
      (libsource (lib "") (part "RES_2"))
    )
    (comp (ref "R115")
      (value "0603-1001-F")
      (footprint "R-SMT-SP-RES/0603")
      (description "贴片电阻")
      (libsource (lib "*") (part "RES"))
    )
    (comp (ref "R116")
      (value "0603-2001-F")
      (footprint "R-SMT-SP-RES/0603")
      (description "贴片电阻")
      (libsource (lib "*") (part "RES"))
    )
    (comp (ref "R117")
      (value "0603-1501-F")
      (footprint "R-SMT-SP-RES/0603")
      (description "贴片电阻")
      (libsource (lib "*") (part "RES"))
    )
    (comp (ref "R118")
      (value "0603-2001-F")
      (footprint "R-SMT-SP-RES/0603")
      (description "贴片电阻")
      (libsource (lib "*") (part "RES"))
    )
    (comp (ref "R119")
      (value "0603-4301-F")
      (footprint "R-SMT-SP-RES/0603")
      (description "贴片电阻")
      (libsource (lib "*") (part "RES1"))
    )
    (comp (ref "R121")
      (value "0603-2001-F")
      (footprint "R-SMT-SP-RES/0603")
      (description "贴片电阻")
      (libsource (lib "*") (part "RES5"))
    )
    (comp (ref "R122")
      (value "0603-8061-F")
      (footprint "R-SMT-SP-RES/0603")
      (description "贴片电阻")
      (libsource (lib "*") (part "RES5"))
    )
    (comp (ref "R123")
      (value "0603-5101-F")
      (footprint "R-SMT-SP-RES/0603")
      (description "贴片电阻")
      (libsource (lib "*") (part "RES"))
    )
    (comp (ref "R124")
      (value "0603-1002-F")
      (footprint "R-SMT-SP-RES/0603")
      (description "贴片电阻")
      (libsource (lib "*") (part "RES5"))
    )
    (comp (ref "R125")
      (value "0603-202-J")
      (footprint "R-SMT-SP-RES/0603")
      (description "贴片电阻")
      (libsource (lib "*") (part "RES"))
    )
    (comp (ref "R126")
      (value "0603-1002-F")
      (footprint "R-SMT-SP-RES/0603")
      (description "贴片电阻")
      (libsource (lib "*") (part "RES5"))
    )
    (comp (ref "R127")
      (value "0603-202-J")
      (footprint "R-SMT-SP-RES/0603")
      (description "贴片电阻")
      (libsource (lib "*") (part "RES"))
    )
    (comp (ref "R134") (value "0603-103-F") (footprint "R/0603-SMT") (libsource (lib "*") (part "RES5")))
    (comp (ref "R135") (value "0603-103-F") (footprint "R/0603-SMT") (libsource (lib "*") (part "RES5")))
    (comp (ref "R136") (value "0603-101-F") (footprint "R/0603-SMT") (libsource (lib "*") (part "RES5")))
    (comp (ref "R137") (value "0603-101-F") (footprint "R/0603-SMT") (libsource (lib "*") (part "RES5")))
    (comp (ref "R138")
      (value "0603-1001-F")
      (footprint "R-SMT-SP-RES/0603")
      (description "贴片电阻")
      (fields (field (name "PUBLISHER") "Altium Limited"))
      (libsource (lib "") (part "Res2_2"))
    )
    (comp (ref "R139")
      (value "0603-152-J")
      (footprint "R-SMT-SP-RES/0603")
      (description "贴片电阻")
      (fields (field (name "PUBLISHER") "Altium Limited"))
      (libsource (lib "Miscellaneous Devices") (part "Res2"))
    )
    (comp (ref "R140")
      (value "0603-1202-F")
      (footprint "R-SMT-SP-RES/0603")
      (description "贴片电阻")
      (libsource (lib "*") (part "RES5"))
    )
    (comp (ref "R141")
      (value "0603-102-J")
      (footprint "R-SMT-SP-RES/0603")
      (description "贴片电阻")
      (libsource (lib "*") (part "RES"))
    )
    (comp (ref "R142")
      (value "0603-332-J")
      (footprint "R-SMT-SP-RES/0603")
      (description "贴片电阻")
      (fields (field (name "PUBLISHER") "Altium Limited"))
      (libsource (lib "Miscellaneous Devices") (part "Res2"))
    )
    (comp (ref "R143")
      (value "0603-101-J")
      (footprint "R-SMT-SP-RES/0603")
      (description "贴片电阻")
      (libsource (lib "*") (part "RES"))
    )
    (comp (ref "R144")
      (value "0603-101-J")
      (footprint "R-SMT-SP-RES/0603")
      (description "贴片电阻")
      (libsource (lib "*") (part "RES"))
    )
    (comp (ref "R145")
      (value "0603-561-J")
      (footprint "R-SMT-SP-RES/0603")
      (description "贴片电阻")
      (fields (field (name "PUBLISHER") "Altium Limited"))
      (libsource (lib "") (part "Res2_1"))
    )
    (comp (ref "R146")
      (value "2K±5%")
      (footprint "S-R/5/2W/R1-AI")
      (description "松下氧化膜电阻")
      (fields (field (name "PUBLISHER") "Altium Limited"))
      (libsource (lib "") (part "Res2_1"))
    )
    (comp (ref "R147")
      (value "0603-101-J")
      (footprint "R-SMT-SP-RES/0603")
      (description "贴片电阻")
      (libsource (lib "*") (part "RES"))
    )
    (comp (ref "R148")
      (value "0603-101-J")
      (footprint "R-SMT-SP-RES/0603")
      (description "贴片电阻")
      (libsource (lib "*") (part "RES"))
    )
    (comp (ref "R149")
      (value "0603-1202-F")
      (footprint "R-SMT-SP-RES/0603")
      (description "贴片电阻")
      (fields (field (name "PUBLISHER") "Altium Limited"))
      (libsource (lib "Miscellaneous Devices") (part "Res2"))
    )
    (comp (ref "R150")
      (value "0603-101-J")
      (footprint "R-SMT-SP-RES/0603")
      (description "贴片电阻")
      (libsource (lib "*") (part "RES"))
    )
    (comp (ref "R151")
      (value "3W-2K±5%")
      (footprint "S-R/10/3W-AI")
      (description "松下氧化膜电阻")
      (fields (field (name "PUBLISHER") "Altium Limited"))
      (libsource (lib "") (part "Res2_1"))
    )
    (comp (ref "R152")
      (value "0603-101-J")
      (footprint "R-SMT-SP-RES/0603")
      (description "贴片电阻")
      (libsource (lib "*") (part "RES"))
    )
    (comp (ref "R153")
      (value "0603-2001-F")
      (footprint "R-SMT-SP-RES/0603")
      (description "贴片电阻")
      (fields (field (name "PUBLISHER") "Altium Limited"))
      (libsource (lib "") (part "Res2_1"))
    )
    (comp (ref "R160")
      (value "0603-5101-F")
      (footprint "R-SMT-SP-RES/0603")
      (description "贴片电阻")
      (fields (field (name "PUBLISHER") "Altium Limited"))
      (libsource (lib "Miscellaneous Devices") (part "Res2"))
    )
    (comp (ref "R161")
      (value "0603-1002-F")
      (footprint "R-SMT-SP-RES/0603")
      (description "贴片电阻")
      (libsource (lib "*") (part "RES5"))
    )
    (comp (ref "R162")
      (value "0603-3001-J")
      (footprint "R-SMT-SP-RES/0603")
      (description "贴片电阻")
      (libsource (lib "*") (part "RES"))
    )
    (comp (ref "R165")
      (value "2512-1.2Ω±1%/1W")
      (footprint "R/2512-SMT")
      (description "贴片电阻")
      (libsource (lib "*") (part "RES"))
    )
    (comp (ref "R168")
      (value "0603-1001-F")
      (footprint "R-SMT-SP-RES/0603")
      (description "贴片电阻")
      (libsource (lib "*") (part "RES5"))
    )
    (comp (ref "R169")
      (value "0603-1201-F")
      (footprint "R-SMT-SP-RES/0603")
      (description "贴片电阻")
      (libsource (lib "*") (part "RES5"))
    )
    (comp (ref "R170")
      (value "0603-1001-F")
      (footprint "R-SMT-SP-RES/0603")
      (description "贴片电阻")
      (libsource (lib "*") (part "RES5"))
    )
    (comp (ref "R171")
      (value "0603-1002-F")
      (footprint "R-SMT-SP-RES/0603")
      (description "贴片电阻")
      (libsource (lib "*") (part "RES5"))
    )
    (comp (ref "R174")
      (value "0603-1001-F")
      (footprint "R-SMT-SP-RES/0603")
      (description "贴片电阻")
      (libsource (lib "*") (part "RES5"))
    )
    (comp (ref "R176")
      (value "0603-20R-J")
      (footprint "R-SMT-SP-RES/0603")
      (description "贴片电阻")
      (libsource (lib "*") (part "RES5"))
    )
    (comp (ref "R180")
      (value "0603-20R-J")
      (footprint "R-SMT-SP-RES/0603")
      (description "贴片电阻")
      (libsource (lib "*") (part "RES5"))
    )
    (comp (ref "RA7")
      (value "0603-2001-F")
      (footprint "R-SMT-SP-RES/0603")
      (description "贴片电阻")
      (libsource (lib "*") (part "RES"))
    )
    (comp (ref "RB0")
      (value "0603-5101-F")
      (footprint "R-SMT-SP-RES/0603")
      (description "贴片电阻")
      (libsource (lib "*") (part "RES"))
    )
    (comp (ref "RY1")
      (value "JDQ-SS-112V/16A-O-T85-P35-B")
      (footprint "RY/OJE-SS")
      (libsource (lib "原理图库") (part "RY-继电器"))
    )
    (comp (ref "RY4")
      (value "SRB-S-112DM")
      (footprint "RY/G5N-1A")
      (description "RELAY")
      (libsource (lib "*") (part "RELAY-SPST"))
    )
    (comp (ref "RY5")
      (value "SRB-S-112DM")
      (footprint "RY/G5N-1A")
      (description "RELAY")
      (libsource (lib "*") (part "RELAY-SPST"))
    )
    (comp (ref "T1")
      (value "EE19(6+2)1P3.5-0.6W1")
      (footprint "S-TR/EE1905N111")
      (description "TRANSFORM")
      (libsource (lib "EE1905") (part "TRANS9"))
    )
    (comp (ref "U1")
      (value "HIP1506YSA-T")
      (footprint "IPM/HIP1506YSA-T")
      (fields (field (name "ALTIUM_UNNAMED_1") "600V/15A"))
      (libsource (lib "原理图库SCHLIB") (part "IPM/HIP1506YSA-T"))
    )
    (comp (ref "U2")
      (value "SH32F205_M80")
      (footprint "IC/LQFP80L")
      (libsource (lib "原理图库SCHLIB") (part "IC/SH32F205/PIN80"))
    )
    (comp (ref "U3")
      (value "ULN2003A")
      (footprint "IC/SOP/1.27/16-SMT")
      (description "Driver")
      (libsource (lib "*") (part "62003"))
    )
    (comp (ref "U4")
      (value "IPM/HIP0306YDM")
      (footprint "IPM/HIP0306YDM")
      (fields (field (name "ALTIUM_UNNAMED_1") "600V/3A"))
      (libsource (lib "原理图库SCHLIB") (part "IPM/HIP0306YDM"))
    )
    (comp (ref "ZR1")
      (value "14D621±10%-D")
      (footprint "S-ZR/7.5/8/15-AI")
      (description "ZR")
      (libsource (lib "*") (part "ZR(DNR)"))
    )
    (comp (ref "ZR2")
      (value "14D621±10%-D")
      (footprint "S-ZR/7.5/8/15-AI")
      (description "ZR")
      (libsource (lib "*") (part "ZR(DNR)"))
    )
  )
  (nets
    (net (code "1") (name "+12V") (class "Default")
      (node (ref "C43") (pin "1") (pinfunction "1_1") (pintype "passive"))
      (node (ref "C5") (pin "2") (pinfunction "2_2") (pintype "passive"))
      (node (ref "CN9") (pin "5") (pinfunction "5_5") (pintype "passive"))
      (node (ref "CN9") (pin "6") (pinfunction "6_6") (pintype "passive"))
      (node (ref "D1") (pin "K") (pinfunction "K_K") (pintype "passive"))
      (node (ref "D3") (pin "K") (pinfunction "K_K") (pintype "passive"))
      (node (ref "D7") (pin "K") (pinfunction "K_K") (pintype "passive"))
      (node (ref "E3") (pin "1") (pinfunction "1_1") (pintype "passive"))
      (node (ref "IC1") (pin "1") (pinfunction "(1)Vin_1") (pintype "passive"))
      (node (ref "R1") (pin "1") (pinfunction "1_1") (pintype "passive"))
      (node (ref "R2") (pin "1") (pinfunction "1_1") (pintype "passive"))
      (node (ref "R3") (pin "1") (pinfunction "1_1") (pintype "passive"))
      (node (ref "R5") (pin "1") (pinfunction "1_1") (pintype "passive"))
      (node (ref "R7") (pin "2") (pinfunction "2_2") (pintype "passive"))
      (node (ref "R9") (pin "2") (pinfunction "2_2") (pintype "passive"))
      (node (ref "RY1") (pin "1") (pintype "passive"))
      (node (ref "RY4") (pin "3") (pinfunction "3_3") (pintype "passive"))
      (node (ref "RY5") (pin "3") (pinfunction "3_3") (pintype "passive"))
      (node (ref "U3") (pin "9") (pinfunction "V_9") (pintype "passive"))
    )
    (net (code "2") (name "+15V") (class "Default")
      (node (ref "C29") (pin "1") (pinfunction "1_1") (pintype "passive"))
      (node (ref "C30") (pin "1") (pinfunction "1_1") (pintype "passive"))
      (node (ref "C87") (pin "1") (pinfunction "1_1") (pintype "passive"))
      (node (ref "C88") (pin "1") (pinfunction "1_1") (pintype "passive"))
      (node (ref "C9") (pin "1") (pinfunction "1_1") (pintype "passive"))
      (node (ref "D8") (pin "A") (pinfunction "A_A") (pintype "passive"))
      (node (ref "E20") (pin "1") (pinfunction "1_1") (pintype "passive"))
      (node (ref "E6") (pin "1") (pinfunction "1_1") (pintype "passive"))
      (node (ref "E8") (pin "1") (pinfunction "1_1") (pintype "passive"))
      (node (ref "IC2") (pin "3") (pinfunction "(3)Vout_3") (pintype "passive"))
      (node (ref "U1") (pin "34") (pinfunction "VDD_34") (pintype "passive"))
      (node (ref "U4") (pin "2") (pinfunction "VDD_2") (pintype "passive"))
    )
    (net (code "3") (name "/4WAY") (class "Default")
      (node (ref "U2") (pin "77") (pinfunction "CP2P2/ADC3_AN0/PD15_77") (pintype "passive"))
      (node (ref "U3") (pin "6") (pinfunction "6B_6") (pintype "input"))
    )
    (net (code "4") (name "/4WAY'") (class "Default")
      (node (ref "RY5") (pin "4") (pinfunction "4_4") (pintype "passive"))
      (node (ref "U3") (pin "11") (pinfunction "6C_11") (pintype "open_collector"))
    )
    (net (code "5") (name "/AC-L") (class "Default")
      (node (ref "C11") (pin "2") (pinfunction "2_2") (pintype "passive"))
      (node (ref "C7") (pin "1") (pinfunction "1_1") (pintype "passive"))
      (node (ref "L1") (pin "4") (pinfunction "4_4") (pintype "passive"))
      (node (ref "PTC1") (pin "1") (pinfunction "1_1") (pintype "passive"))
      (node (ref "RY1") (pin "4") (pintype "passive"))
    )
    (net (code "6") (name "/AC-L1") (class "Default")
      (node (ref "GBJ1") (pin "3") (pinfunction "AC_3") (pintype "passive"))
      (node (ref "PTC1") (pin "2") (pinfunction "2_2") (pintype "passive"))
      (node (ref "R10") (pin "1") (pinfunction "1_1") (pintype "passive"))
      (node (ref "RY1") (pin "3") (pintype "passive"))
    )
    (net (code "7") (name "/AC-N") (class "Default")
      (node (ref "C14") (pin "2") (pinfunction "2_2") (pintype "passive"))
      (node (ref "C7") (pin "2") (pinfunction "2_2") (pintype "passive"))
      (node (ref "GBJ1") (pin "2") (pinfunction "AC_2") (pintype "passive"))
      (node (ref "L1") (pin "3") (pinfunction "3_3") (pintype "passive"))
      (node (ref "R11") (pin "1") (pinfunction "1_1") (pintype "passive"))
    )
    (net (code "8") (name "/ACL-IN") (class "Default")
      (node (ref "C8") (pin "1") (pinfunction "1_1") (pintype "passive"))
      (node (ref "FUSE1") (pin "2") (pinfunction "2_2") (pintype "passive"))
      (node (ref "L1") (pin "2") (pinfunction "2_2") (pintype "passive"))
      (node (ref "RY4") (pin "1") (pinfunction "1_1") (pintype "passive"))
      (node (ref "RY5") (pin "1") (pinfunction "1_1") (pintype "passive"))
      (node (ref "ZR2") (pin "1") (pinfunction "1_1") (pintype "passive"))
    )
    (net (code "9") (name "/ACN-IN") (class "Default")
      (node (ref "C70") (pin "2") (pintype "passive"))
      (node (ref "C75") (pin "1") (pintype "passive"))
      (node (ref "C8") (pin "2") (pinfunction "2_2") (pintype "passive"))
      (node (ref "CN1") (pin "1") (pinfunction "1_1") (pintype "passive"))
      (node (ref "CN5") (pin "1") (pinfunction "1_1") (pintype "passive"))
      (node (ref "CN8") (pin "2") (pinfunction "2_2") (pintype "passive"))
      (node (ref "D15") (pin "K") (pinfunction "K_K") (pintype "passive"))
      (node (ref "IC8") (pin "A") (pinfunction "A_A") (pintype "passive"))
      (node (ref "L1") (pin "1") (pinfunction "1_1") (pintype "passive"))
      (node (ref "R139") (pin "1") (pinfunction "1_1") (pintype "passive"))
      (node (ref "ZR1") (pin "1") (pinfunction "1_1") (pintype "passive"))
      (node (ref "ZR2") (pin "2") (pinfunction "2_2") (pintype "passive"))
    )
    (net (code "10") (name "/COMP_CP3N") (class "Default")
      (node (ref "R115") (pin "2") (pinfunction "2_2") (pintype "passive"))
      (node (ref "R116") (pin "1") (pinfunction "1_1") (pintype "passive"))
      (node (ref "U2") (pin "54") (pinfunction "PC11/ADC2_AN7/CP3N_54") (pintype "passive"))
    )
    (net (code "11") (name "/COMP_CP3P") (class "Default")
      (node (ref "R106") (pin "2") (pinfunction "2_2") (pintype "passive"))
      (node (ref "RA7") (pin "1") (pinfunction "1_1") (pintype "passive"))
      (node (ref "U2") (pin "55") (pinfunction "PC12/ADC2_AN6/CP3P0_55") (pintype "passive"))
    )
    (net (code "12") (name "/COMP_FAULT") (class "Default")
      (node (ref "C31") (pin "2") (pinfunction "2_2") (pintype "passive"))
      (node (ref "R46") (pin "1") (pinfunction "1_1") (pintype "passive"))
      (node (ref "U2") (pin "34") (pinfunction "PB7/MCM1_FLT_34") (pintype "passive"))
    )
    (net (code "13") (name "/COMP_Temp") (class "Default")
      (node (ref "C36") (pin "2") (pinfunction "2_2") (pintype "passive"))
      (node (ref "R51") (pin "1") (pinfunction "1_1") (pintype "passive"))
      (node (ref "U2") (pin "53") (pinfunction "PC10/ADC23_AN8/CP3OUT_53") (pintype "passive"))
    )
    (net (code "14") (name "/COMP_UH") (class "Default")
      (node (ref "R53") (pin "1") (pinfunction "1_1") (pintype "passive"))
      (node (ref "U2") (pin "40") (pinfunction "PB13/MCM1_PWM0_40") (pintype "passive"))
    )
    (net (code "15") (name "/COMP_UL") (class "Default")
      (node (ref "R56") (pin "1") (pinfunction "1_1") (pintype "passive"))
      (node (ref "U2") (pin "37") (pinfunction "PB10/MCM1_PWM01_37") (pintype "passive"))
    )
    (net (code "16") (name "/COMP_VH") (class "Default")
      (node (ref "R54") (pin "1") (pinfunction "1_1") (pintype "passive"))
      (node (ref "U2") (pin "39") (pinfunction "PB12/MCM1_PWM1_39") (pintype "passive"))
    )
    (net (code "17") (name "/COMP_VL") (class "Default")
      (node (ref "R58") (pin "1") (pinfunction "1_1") (pintype "passive"))
      (node (ref "U2") (pin "36") (pinfunction "PB9/MCM1_PWM11_36") (pintype "passive"))
    )
    (net (code "18") (name "/COMP_WH") (class "Default")
      (node (ref "R55") (pin "1") (pinfunction "1_1") (pintype "passive"))
      (node (ref "U2") (pin "38") (pinfunction "PB11/MCM1_PWM2_38") (pintype "passive"))
    )
    (net (code "19") (name "/COMP_WL") (class "Default")
      (node (ref "R61") (pin "1") (pinfunction "1_1") (pintype "passive"))
      (node (ref "U2") (pin "35") (pinfunction "PB8/MCM1_PWM21_35") (pintype "passive"))
    )
    (net (code "20") (name "/EEV1") (class "Default")
      (node (ref "U2") (pin "75") (pinfunction "ADC1_AN6/PD13_75") (pintype "passive"))
      (node (ref "U3") (pin "2") (pinfunction "2B_2") (pintype "input"))
    )
    (net (code "21") (name "/EEV2") (class "Default")
      (node (ref "U2") (pin "74") (pinfunction "ADC1_AN5/PD12_74") (pintype "passive"))
      (node (ref "U3") (pin "3") (pinfunction "3B_3") (pintype "input"))
    )
    (net (code "22") (name "/EEV3") (class "Default")
      (node (ref "U2") (pin "73") (pinfunction "ADC1_AN4/PD11_73") (pintype "passive"))
      (node (ref "U3") (pin "4") (pinfunction "4B_4") (pintype "input"))
    )
    (net (code "23") (name "/EEV4") (class "Default")
      (node (ref "U2") (pin "72") (pinfunction "ADC1_AN3/PD10_72") (pintype "passive"))
      (node (ref "U3") (pin "5") (pinfunction "5B_5") (pintype "input"))
    )
    (net (code "24") (name "/FAN_FAULT") (class "Default")
      (node (ref "C89") (pin "1") (pinfunction "1_1") (pintype "passive"))
      (node (ref "R162") (pin "1") (pinfunction "1_1") (pintype "passive"))
      (node (ref "U2") (pin "47") (pinfunction "PC4/MCM2_FLT_47") (pintype "passive"))
    )
    (net (code "25") (name "/FAN_Temp") (class "Default")
      (node (ref "C71") (pin "2") (pinfunction "2_2") (pintype "passive"))
      (node (ref "R141") (pin "1") (pinfunction "1_1") (pintype "passive"))
      (node (ref "U2") (pin "52") (pinfunction "PC9/ADC23_AN9_52") (pintype "passive"))
    )
    (net (code "26") (name "/FAN_UH") (class "Default")
      (node (ref "R143") (pin "1") (pinfunction "1_1") (pintype "passive"))
      (node (ref "U2") (pin "46") (pinfunction "PC3/MCM2_PWM0_46") (pintype "passive"))
    )
    (net (code "27") (name "/FAN_UL") (class "Default")
      (node (ref "R148") (pin "1") (pinfunction "1_1") (pintype "passive"))
      (node (ref "U2") (pin "43") (pinfunction "PC0/MCM2_PWM01_43") (pintype "passive"))
    )
    (net (code "28") (name "/FAN_VH") (class "Default")
      (node (ref "R144") (pin "1") (pinfunction "1_1") (pintype "passive"))
      (node (ref "U2") (pin "45") (pinfunction "PC2/MCM2_PWM1_45") (pintype "passive"))
    )
    (net (code "29") (name "/FAN_VL") (class "Default")
      (node (ref "R150") (pin "1") (pinfunction "1_1") (pintype "passive"))
      (node (ref "U2") (pin "42") (pinfunction "PB15/MCM2_PWM11_42") (pintype "passive"))
    )
    (net (code "30") (name "/FAN_WH") (class "Default")
      (node (ref "R147") (pin "1") (pinfunction "1_1") (pintype "passive"))
      (node (ref "U2") (pin "44") (pinfunction "PC1/MCM2_PWM2_44") (pintype "passive"))
    )
    (net (code "31") (name "/FAN_WL") (class "Default")
      (node (ref "R152") (pin "1") (pinfunction "1_1") (pintype "passive"))
      (node (ref "U2") (pin "41") (pinfunction "PB14/MCM2_PWM21_41") (pintype "passive"))
    )
    (net (code "32") (name "/HEAT") (class "Default")
      (node (ref "U2") (pin "78") (pinfunction "CP2P1/ADC3_AN1/PE0_78") (pintype "passive"))
      (node (ref "U3") (pin "7") (pinfunction "7B_7") (pintype "input"))
    )
    (net (code "33") (name "/I_COMP_N") (class "Default")
      (node (ref "U2") (pin "64") (pinfunction "OP2N/PD2_64") (pintype "passive"))
    )
    (net (code "34") (name "/I_COMP_OUT") (class "Default")
      (node (ref "C59") (pin "1") (pinfunction "1_1") (pintype "passive"))
      (node (ref "C61") (pin "1") (pinfunction "1_1") (pintype "passive"))
      (node (ref "R102") (pin "1") (pinfunction "1_1") (pintype "passive"))
      (node (ref "R113") (pin "1") (pinfunction "1_1") (pintype "passive"))
      (node (ref "R66") (pin "2") (pinfunction "2_2") (pintype "passive"))
      (node (ref "U2") (pin "63") (pinfunction "OP2OUT/PD1_63") (pintype "passive"))
    )
    (net (code "35") (name "/I_COMP_P") (class "Default")
      (node (ref "R88") (pin "2") (pinfunction "2_2") (pintype "passive"))
      (node (ref "R89") (pin "1") (pinfunction "1_1") (pintype "passive"))
      (node (ref "R97") (pin "1") (pinfunction "1_1") (pintype "passive"))
      (node (ref "U2") (pin "65") (pinfunction "OP2P/PD3_65") (pintype "passive"))
    )
    (net (code "36") (name "/I_FAN") (class "Default")
      (node (ref "C90") (pin "1") (pinfunction "1_1") (pintype "passive"))
      (node (ref "R170") (pin "2") (pinfunction "2_2") (pintype "passive"))
      (node (ref "R171") (pin "1") (pinfunction "1_1") (pintype "passive"))
      (node (ref "U2") (pin "48") (pinfunction "PC5/ADC3_AN4/MCM2_SC1/ADTRG1_48") (pintype "passive"))
    )
    (net (code "37") (name "/I_PFC_N") (class "Default")
      (node (ref "C54") (pin "2") (pinfunction "2_2") (pintype "passive"))
      (node (ref "R83") (pin "1") (pinfunction "1_1") (pintype "passive"))
      (node (ref "R84") (pin "2") (pinfunction "2_2") (pintype "passive"))
      (node (ref "R91") (pin "2") (pinfunction "2_2") (pintype "passive"))
      (node (ref "U2") (pin "67") (pinfunction "OP1N/PD5_67") (pintype "passive"))
    )
    (net (code "38") (name "/I_PFC_OUT") (class "Default")
      (node (ref "C53") (pin "1") (pinfunction "1_1") (pintype "passive"))
      (node (ref "C54") (pin "1") (pinfunction "1_1") (pintype "passive"))
      (node (ref "R84") (pin "1") (pinfunction "1_1") (pintype "passive"))
      (node (ref "R86") (pin "1") (pinfunction "1_1") (pintype "passive"))
      (node (ref "R91") (pin "1") (pinfunction "1_1") (pintype "passive"))
      (node (ref "U2") (pin "66") (pinfunction "OP1OUT/PD4_66") (pintype "passive"))
    )
    (net (code "39") (name "/I_PFC_P") (class "Default")
      (node (ref "R63") (pin "1") (pinfunction "1_1") (pintype "passive"))
      (node (ref "R64") (pin "2") (pinfunction "2_2") (pintype "passive"))
      (node (ref "R77") (pin "1") (pinfunction "1_1") (pintype "passive"))
      (node (ref "U2") (pin "68") (pinfunction "CP1P1/OP1P/PD6_68") (pintype "passive"))
    )
    (net (code "40") (name "/NRST") (class "Default")
      (node (ref "C63") (pin "1") (pinfunction "1_1") (pintype "passive"))
      (node (ref "R126") (pin "2") (pinfunction "2_2") (pintype "passive"))
      (node (ref "U2") (pin "6") (pinfunction "NRST_6") (pintype "passive"))
    )
    (net (code "41") (name "/PFC_CP2N") (class "Default")
      (node (ref "R108") (pin "2") (pinfunction "2_2") (pintype "passive"))
      (node (ref "R109") (pin "1") (pinfunction "1_1") (pintype "passive"))
      (node (ref "U2") (pin "80") (pinfunction "CP2N/ADC3_AN3/PE2_80") (pintype "passive"))
    )
    (net (code "42") (name "/PFC_CP2P") (class "Default")
      (node (ref "R117") (pin "2") (pinfunction "2_2") (pintype "passive"))
      (node (ref "R118") (pin "1") (pinfunction "1_1") (pintype "passive"))
      (node (ref "U2") (pin "79") (pinfunction "CP2P0/ADC3_AN2/PE1_79") (pintype "passive"))
    )
    (net (code "43") (name "/PFC_PWM") (class "Default")
      (node (ref "R52") (pin "1") (pinfunction "1_1") (pintype "passive"))
      (node (ref "U2") (pin "26") (pinfunction "PA15/GTIOC2B/MISO1_26") (pintype "passive"))
    )
    (net (code "44") (name "/POWER_ON_RELAY") (class "Default")
      (node (ref "U2") (pin "76") (pinfunction "ADC1_AN7/PD14_76") (pintype "passive"))
      (node (ref "U3") (pin "1") (pinfunction "1B_1") (pintype "input"))
    )
    (net (code "45") (name "/POWER_ON_RELAY'") (class "Default")
      (node (ref "RY1") (pin "2") (pintype "passive"))
      (node (ref "U3") (pin "16") (pinfunction "1C_16") (pintype "open_collector"))
    )
    (net (code "46") (name "/RXD1") (class "Default")
      (node (ref "C73") (pin "1") (pintype "passive"))
      (node (ref "R138") (pin "2") (pinfunction "2_2") (pintype "passive"))
      (node (ref "U2") (pin "18") (pinfunction "QEB/GTIOC3B1/RXD2/PA8_18") (pintype "passive"))
    )
    (net (code "47") (name "/SWC") (class "Default")
      (node (ref "R176") (pin "2") (pinfunction "2_2") (pintype "passive"))
      (node (ref "U2") (pin "15") (pinfunction "SWCLK/JTCK/PA5_15") (pintype "passive"))
    )
    (net (code "48") (name "/SWD") (class "Default")
      (node (ref "R180") (pin "2") (pinfunction "2_2") (pintype "passive"))
      (node (ref "U2") (pin "14") (pinfunction "SWDIO/JTMS/PA4_14") (pintype "passive"))
    )
    (net (code "49") (name "/T3") (class "Default")
      (node (ref "C57") (pin "2") (pinfunction "2_2") (pintype "passive"))
      (node (ref "R94") (pin "2") (pinfunction "2_2") (pintype "passive"))
      (node (ref "U2") (pin "51") (pinfunction "PC8/ADC3_AN7_51") (pintype "passive"))
    )
    (net (code "50") (name "/T4") (class "Default")
      (node (ref "C60") (pin "2") (pinfunction "2_2") (pintype "passive"))
      (node (ref "R111") (pin "2") (pinfunction "2_2") (pintype "passive"))
      (node (ref "U2") (pin "50") (pinfunction "PC7/ADC3_AN6/MCM2_SC3/ADTRG3_50") (pintype "passive"))
    )
    (net (code "51") (name "/TEST-CLK") (class "Default")
      (node (ref "C68") (pin "2") (pinfunction "2_2") (pintype "passive"))
      (node (ref "R136") (pin "2") (pinfunction "2_2") (pintype "passive"))
      (node (ref "U2") (pin "28") (pinfunction "PB1/SCL1/T_28") (pintype "passive"))
    )
    (net (code "52") (name "/TEST-DATA") (class "Default")
      (node (ref "C67") (pin "2") (pinfunction "2_2") (pintype "passive"))
      (node (ref "R137") (pin "2") (pinfunction "2_2") (pintype "passive"))
      (node (ref "U2") (pin "27") (pinfunction "PB0/SDA1/T5_27") (pintype "passive"))
    )
    (net (code "53") (name "/TP") (class "Default")
      (node (ref "C62") (pin "1") (pinfunction "1_1") (pintype "passive"))
      (node (ref "R121") (pin "1") (pinfunction "1_1") (pintype "passive"))
      (node (ref "U2") (pin "49") (pinfunction "PC6/ADC3_AN5/MCM2_SC2/ADTRG2_49") (pintype "passive"))
    )
    (net (code "54") (name "/TXD1") (class "Default")
      (node (ref "R153") (pin "1") (pinfunction "1_1") (pintype "passive"))
      (node (ref "U2") (pin "20") (pinfunction "INDEX/GTIOC3B2/TXD2/PA9_20") (pintype "passive"))
    )
    (net (code "55") (name "/U_COMP") (class "Default")
      (node (ref "C39") (pin "2") (pinfunction "2_2") (pintype "passive"))
      (node (ref "CN4") (pin "3") (pinfunction "3_3") (pintype "passive"))
      (node (ref "E11") (pin "2") (pinfunction "2_2") (pintype "passive"))
      (node (ref "U1") (pin "13") (pinfunction "U_13") (pintype "passive"))
    )
    (net (code "56") (name "/U_FAN") (class "Default")
      (node (ref "C76") (pin "2") (pinfunction "2_2") (pintype "passive"))
      (node (ref "CN14") (pin "1") (pinfunction "1_1") (pintype "passive"))
      (node (ref "E17") (pin "2") (pinfunction "2_2") (pintype "passive"))
      (node (ref "U4") (pin "32") (pinfunction "U,VS1_32") (pintype "passive"))
    )
    (net (code "57") (name "/VCS") (class "Default")
      (node (ref "R104") (pin "2") (pinfunction "2_2") (pintype "passive"))
      (node (ref "R105") (pin "1") (pinfunction "1_1") (pintype "passive"))
      (node (ref "R48") (pin "1") (pinfunction "1_1") (pintype "passive"))
      (node (ref "R85") (pin "2") (pinfunction "2_2") (pintype "passive"))
      (node (ref "U1") (pin "21") (pinfunction "NW_21") (pintype "passive"))
      (node (ref "U1") (pin "22") (pinfunction "NV_22") (pintype "passive"))
      (node (ref "U1") (pin "23") (pinfunction "NU_23") (pintype "passive"))
    )
    (net (code "58") (name "/VREF") (class "Default")
      (node (ref "C32") (pin "1") (pinfunction "1_1") (pintype "passive"))
      (node (ref "C33") (pin "1") (pinfunction "1_1") (pintype "passive"))
      (node (ref "U2") (pin "57") (pinfunction "CVREF_57") (pintype "passive"))
    )
    (net (code "59") (name "/V_AC_N") (class "Default")
      (node (ref "C19") (pin "2") (pinfunction "2_2") (pintype "passive"))
      (node (ref "C20") (pin "2") (pinfunction "2_2") (pintype "passive"))
      (node (ref "D5") (pin "A") (pinfunction "A_A") (pintype "passive"))
      (node (ref "D5") (pin "K") (pinfunction "K_K") (pintype "passive"))
      (node (ref "R22") (pin "2") (pinfunction "2_2") (pintype "passive"))
      (node (ref "R27") (pin "2") (pinfunction "2_2") (pintype "passive"))
      (node (ref "R29") (pin "2") (pinfunction "2_2") (pintype "passive"))
      (node (ref "U2") (pin "60") (pinfunction "PC14/ADC2_AN4/OP3N_60") (pintype "passive"))
    )
    (net (code "60") (name "/V_AC_OUT") (class "Default")
      (node (ref "C20") (pin "1") (pinfunction "1_1") (pintype "passive"))
      (node (ref "R27") (pin "1") (pinfunction "1_1") (pintype "passive"))
      (node (ref "R29") (pin "1") (pinfunction "1_1") (pintype "passive"))
      (node (ref "R60") (pin "2") (pinfunction "2_2") (pintype "passive"))
      (node (ref "U2") (pin "61") (pinfunction "OP3OUT/ADC2_AN3/PC15_61") (pintype "passive"))
    )
    (net (code "61") (name "/V_AC_P") (class "Default")
      (node (ref "C18") (pin "1") (pinfunction "1_1") (pintype "passive"))
      (node (ref "D5") (pin "KA") (pinfunction "KA_KA") (pintype "passive"))
      (node (ref "R15") (pin "2") (pinfunction "2_2") (pintype "passive"))
      (node (ref "R16") (pin "1") (pinfunction "1_1") (pintype "passive"))
      (node (ref "R21") (pin "2") (pinfunction "2_2") (pintype "passive"))
      (node (ref "U2") (pin "59") (pinfunction "PC13/ADC2_AN5/OP3P/CP3P1_59") (pintype "passive"))
    )
    (net (code "62") (name "/V_COMP") (class "Default")
      (node (ref "C37") (pin "2") (pinfunction "2_2") (pintype "passive"))
      (node (ref "CN4") (pin "2") (pinfunction "2_2") (pintype "passive"))
      (node (ref "E10") (pin "2") (pinfunction "2_2") (pintype "passive"))
      (node (ref "U1") (pin "9") (pinfunction "V_9") (pintype "passive"))
    )
    (net (code "63") (name "/V_DCP") (class "Default")
      (node (ref "C41") (pin "2") (pinfunction "2_2") (pintype "passive"))
      (node (ref "D9") (pin "KA") (pinfunction "KA_KA") (pintype "passive"))
      (node (ref "R57") (pin "1") (pinfunction "1_1") (pintype "passive"))
      (node (ref "U2") (pin "70") (pinfunction "ADC12_AN1/PD8_70") (pintype "passive"))
    )
    (net (code "64") (name "/V_FAN") (class "Default")
      (node (ref "C78") (pin "2") (pinfunction "2_2") (pintype "passive"))
      (node (ref "CN14") (pin "2") (pinfunction "2_2") (pintype "passive"))
      (node (ref "E18") (pin "2") (pinfunction "2_2") (pintype "passive"))
      (node (ref "U4") (pin "26") (pinfunction "V,VS2_26") (pintype "passive"))
    )
    (net (code "65") (name "/W_COMP") (class "Default")
      (node (ref "C35") (pin "2") (pinfunction "2_2") (pintype "passive"))
      (node (ref "CN4") (pin "1") (pinfunction "1_1") (pintype "passive"))
      (node (ref "E9") (pin "2") (pinfunction "2_2") (pintype "passive"))
      (node (ref "U1") (pin "5") (pinfunction "W_5") (pintype "passive"))
    )
    (net (code "66") (name "/W_FAN") (class "Default")
      (node (ref "C85") (pin "2") (pinfunction "2_2") (pintype "passive"))
      (node (ref "CN14") (pin "3") (pinfunction "3_3") (pintype "passive"))
      (node (ref "E19") (pin "2") (pinfunction "2_2") (pintype "passive"))
      (node (ref "U4") (pin "20") (pinfunction "W,VS3_20") (pintype "passive"))
    )
    (net (code "67") (name "1") (class "Default")
      (node (ref "DAS1") (pin "1") (pinfunction "1_1") (pintype "passive"))
      (node (ref "ZR1") (pin "2") (pinfunction "2_2") (pintype "passive"))
    )
    (net (code "68") (name "2") (class "Default")
      (node (ref "C11") (pin "1") (pinfunction "1_1") (pintype "passive"))
      (node (ref "C14") (pin "1") (pinfunction "1_1") (pintype "passive"))
      (node (ref "C15") (pin "2") (pinfunction "2_2") (pintype "passive"))
      (node (ref "CN3") (pin "1") (pinfunction "1_1") (pintype "passive"))
      (node (ref "DAS1") (pin "2") (pinfunction "2_2") (pintype "passive"))
    )
    (net (code "69") (name "BR+") (class "Default")
      (node (ref "C12") (pin "2") (pinfunction "2_2") (pintype "passive"))
      (node (ref "CN7") (pin "1") (pinfunction "1_1") (pintype "passive"))
      (node (ref "GBJ1") (pin "1") (pinfunction "V+_1") (pintype "passive"))
      (node (ref "L2") (pin "2") (pinfunction "2_2") (pintype "passive"))
    )
    (net (code "70") (name "BR-") (class "Default")
      (node (ref "C12") (pin "1") (pinfunction "1_1") (pintype "passive"))
      (node (ref "GBJ1") (pin "4") (pinfunction "V-_4") (pintype "passive"))
      (node (ref "R114") (pin "2") (pinfunction "2_2") (pintype "passive"))
      (node (ref "R81") (pin "2") (pinfunction "2_2") (pintype "passive"))
      (node (ref "R82") (pin "2") (pinfunction "2_2") (pintype "passive"))
      (node (ref "R95") (pin "2") (pinfunction "2_2") (pintype "passive"))
    )
    (net (code "71") (name "GND") (class "Default")
      (node (ref "C1") (pin "1") (pinfunction "1_1") (pintype "passive"))
      (node (ref "C10") (pin "2") (pinfunction "2_2") (pintype "passive"))
      (node (ref "C13") (pin "2") (pinfunction "2_2") (pintype "passive"))
      (node (ref "C17") (pin "1") (pinfunction "1_1") (pintype "passive"))
      (node (ref "C18") (pin "2") (pinfunction "2_2") (pintype "passive"))
      (node (ref "C19") (pin "1") (pinfunction "1_1") (pintype "passive"))
      (node (ref "C21") (pin "1") (pinfunction "1_1") (pintype "passive"))
      (node (ref "C27") (pin "1") (pinfunction "1_1") (pintype "passive"))
      (node (ref "C28") (pin "1") (pinfunction "1_1") (pintype "passive"))
      (node (ref "C29") (pin "2") (pinfunction "2_2") (pintype "passive"))
      (node (ref "C30") (pin "2") (pinfunction "2_2") (pintype "passive"))
      (node (ref "C31") (pin "1") (pinfunction "1_1") (pintype "passive"))
      (node (ref "C32") (pin "2") (pinfunction "2_2") (pintype "passive"))
      (node (ref "C33") (pin "2") (pinfunction "2_2") (pintype "passive"))
      (node (ref "C34") (pin "2") (pinfunction "2_2") (pintype "passive"))
      (node (ref "C36") (pin "1") (pinfunction "1_1") (pintype "passive"))
      (node (ref "C38") (pin "1") (pinfunction "1_1") (pintype "passive"))
      (node (ref "C4") (pin "2") (pinfunction "2_2") (pintype "passive"))
      (node (ref "C40") (pin "1") (pinfunction "1_1") (pintype "passive"))
      (node (ref "C41") (pin "1") (pinfunction "1_1") (pintype "passive"))
      (node (ref "C42") (pin "1") (pinfunction "1_1") (pintype "passive"))
      (node (ref "C43") (pin "2") (pinfunction "2_2") (pintype "passive"))
      (node (ref "C44") (pin "2") (pinfunction "2_2") (pintype "passive"))
      (node (ref "C45") (pin "2") (pinfunction "2_2") (pintype "passive"))
      (node (ref "C46") (pin "2") (pinfunction "2_2") (pintype "passive"))
      (node (ref "C47") (pin "2") (pinfunction "2_2") (pintype "passive"))
      (node (ref "C48") (pin "2") (pinfunction "2_2") (pintype "passive"))
      (node (ref "C49") (pin "2") (pinfunction "2_2") (pintype "passive"))
      (node (ref "C5") (pin "1") (pinfunction "1_1") (pintype "passive"))
      (node (ref "C50") (pin "2") (pinfunction "2_2") (pintype "passive"))
      (node (ref "C51") (pin "2") (pinfunction "2_2") (pintype "passive"))
      (node (ref "C53") (pin "2") (pinfunction "2_2") (pintype "passive"))
      (node (ref "C55") (pin "2") (pinfunction "2_2") (pintype "passive"))
      (node (ref "C56") (pin "1") (pinfunction "1_1") (pintype "passive"))
      (node (ref "C57") (pin "1") (pinfunction "1_1") (pintype "passive"))
      (node (ref "C59") (pin "2") (pinfunction "2_2") (pintype "passive"))
      (node (ref "C6") (pin "1") (pinfunction "1_1") (pintype "passive"))
      (node (ref "C60") (pin "1") (pinfunction "1_1") (pintype "passive"))
      (node (ref "C62") (pin "2") (pinfunction "2_2") (pintype "passive"))
      (node (ref "C63") (pin "2") (pinfunction "2_2") (pintype "passive"))
      (node (ref "C65") (pin "1") (pinfunction "1_1") (pintype "passive"))
      (node (ref "C67") (pin "1") (pinfunction "1_1") (pintype "passive"))
      (node (ref "C68") (pin "1") (pinfunction "1_1") (pintype "passive"))
      (node (ref "C69") (pin "1") (pinfunction "1_1") (pintype "passive"))
      (node (ref "C71") (pin "1") (pinfunction "1_1") (pintype "passive"))
      (node (ref "C72") (pin "2") (pinfunction "2_2") (pintype "passive"))
      (node (ref "C73") (pin "2") (pintype "passive"))
      (node (ref "C74") (pin "2") (pintype "passive"))
      (node (ref "C79") (pin "2") (pinfunction "2_2") (pintype "passive"))
      (node (ref "C80") (pin "2") (pinfunction "2_2") (pintype "passive"))
      (node (ref "C81") (pin "2") (pinfunction "2_2") (pintype "passive"))
      (node (ref "C82") (pin "2") (pinfunction "2_2") (pintype "passive"))
      (node (ref "C83") (pin "2") (pinfunction "2_2") (pintype "passive"))
      (node (ref "C84") (pin "2") (pinfunction "2_2") (pintype "passive"))
      (node (ref "C86") (pin "1") (pinfunction "1_1") (pintype "passive"))
      (node (ref "C87") (pin "2") (pinfunction "2_2") (pintype "passive"))
      (node (ref "C88") (pin "2") (pinfunction "2_2") (pintype "passive"))
      (node (ref "C89") (pin "2") (pinfunction "2_2") (pintype "passive"))
      (node (ref "C9") (pin "2") (pinfunction "2_2") (pintype "passive"))
      (node (ref "C90") (pin "2") (pinfunction "2_2") (pintype "passive"))
      (node (ref "C91") (pin "2") (pinfunction "2_2") (pintype "passive"))
      (node (ref "C92") (pin "1") (pinfunction "1_1") (pintype "passive"))
      (node (ref "CN13") (pin "2") (pinfunction "2_2") (pintype "passive"))
      (node (ref "D10") (pin "A") (pinfunction "A_A") (pintype "passive"))
      (node (ref "D11") (pin "A") (pinfunction "A_A") (pintype "passive"))
      (node (ref "D12") (pin "A") (pinfunction "A_A") (pintype "passive"))
      (node (ref "D9") (pin "A") (pinfunction "A_A") (pintype "passive"))
      (node (ref "E1") (pin "2") (pinfunction "2_2") (pintype "passive"))
      (node (ref "E12") (pin "2") (pinfunction "2_2") (pintype "passive"))
      (node (ref "E14") (pin "2") (pintype "passive"))
      (node (ref "E15") (pin "2") (pintype "passive"))
      (node (ref "E16") (pin "2") (pinfunction "2_2") (pintype "passive"))
      (node (ref "E20") (pin "2") (pinfunction "2_2") (pintype "passive"))
      (node (ref "E3") (pin "2") (pinfunction "2_2") (pintype "passive"))
      (node (ref "E4") (pin "2") (pinfunction "2_2") (pintype "passive"))
      (node (ref "E5") (pin "2") (pinfunction "2_2") (pintype "passive"))
      (node (ref "E6") (pin "2") (pinfunction "2_2") (pintype "passive"))
      (node (ref "E8") (pin "2") (pinfunction "2_2") (pintype "passive"))
      (node (ref "IC1") (pin "2") (pinfunction "(2)GND_2") (pintype "passive"))
      (node (ref "IC2") (pin "2") (pinfunction "(2)GND_2") (pintype "passive"))
      (node (ref "IC3") (pin "2") (pinfunction "BR_2") (pintype "input"))
      (node (ref "IC3") (pin "3") (pinfunction "GND_3") (pintype "input"))
      (node (ref "IC4") (pin "E") (pinfunction "E_E") (pintype "passive"))
      (node (ref "IC5") (pin "2") (pinfunction "2_2") (pintype "passive"))
      (node (ref "J1") (pin "2") (pinfunction "2_2") (pintype "passive"))
      (node (ref "Q6") (pin "E") (pinfunction "E_E") (pintype "passive"))
      (node (ref "R108") (pin "1") (pinfunction "1_1") (pintype "passive"))
      (node (ref "R115") (pin "1") (pinfunction "1_1") (pintype "passive"))
      (node (ref "R119") (pin "2") (pinfunction "2_2") (pintype "passive"))
      (node (ref "R122") (pin "1") (pinfunction "1_1") (pintype "passive"))
      (node (ref "R123") (pin "2") (pinfunction "2_2") (pintype "passive"))
      (node (ref "R124") (pin "1") (pinfunction "1_1") (pintype "passive"))
      (node (ref "R14") (pin "2") (pinfunction "2_2") (pintype "passive"))
      (node (ref "R142") (pin "2") (pinfunction "2_2") (pintype "passive"))
      (node (ref "R15") (pin "1") (pinfunction "1_1") (pintype "passive"))
      (node (ref "R160") (pin "2") (pinfunction "2_2") (pintype "passive"))
      (node (ref "R165") (pin "2") (pinfunction "2_2") (pintype "passive"))
      (node (ref "R174") (pin "1") (pinfunction "1_1") (pintype "passive"))
      (node (ref "R20") (pin "2") (pinfunction "2_2") (pintype "passive"))
      (node (ref "R23") (pin "1") (pinfunction "1_1") (pintype "passive"))
      (node (ref "R24") (pin "2") (pinfunction "2_2") (pintype "passive"))
      (node (ref "R25") (pin "1") (pinfunction "1_1") (pintype "passive"))
      (node (ref "R26") (pin "1") (pinfunction "1_1") (pintype "passive"))
      (node (ref "R28") (pin "1") (pinfunction "1_1") (pintype "passive"))
      (node (ref "R32") (pin "2") (pinfunction "2_2") (pintype "passive"))
      (node (ref "R33") (pin "2") (pinfunction "2_2") (pintype "passive"))
      (node (ref "R34") (pin "1") (pinfunction "1_1") (pintype "passive"))
      (node (ref "R37") (pin "2") (pinfunction "2_2") (pintype "passive"))
      (node (ref "R38") (pin "1") (pinfunction "1_1") (pintype "passive"))
      (node (ref "R39") (pin "1") (pinfunction "1_1") (pintype "passive"))
      (node (ref "R40") (pin "1") (pinfunction "1_1") (pintype "passive"))
      (node (ref "R42") (pin "1") (pinfunction "1_1") (pintype "passive"))
      (node (ref "R62") (pin "1") (pinfunction "1_1") (pintype "passive"))
      (node (ref "R64") (pin "1") (pinfunction "1_1") (pintype "passive"))
      (node (ref "R74") (pin "1") (pinfunction "1_1") (pintype "passive"))
      (node (ref "R76") (pin "2") (pinfunction "2_2") (pintype "passive"))
      (node (ref "R78") (pin "1") (pinfunction "1_1") (pintype "passive"))
      (node (ref "R79") (pin "1") (pinfunction "1_1") (pintype "passive"))
      (node (ref "R8") (pin "2") (pinfunction "2_2") (pintype "passive"))
      (node (ref "R81") (pin "1") (pinfunction "1_1") (pintype "passive"))
      (node (ref "R85") (pin "1") (pinfunction "1_1") (pintype "passive"))
      (node (ref "R88") (pin "1") (pinfunction "1_1") (pintype "passive"))
      (node (ref "R98") (pin "2") (pinfunction "2_2") (pintype "passive"))
      (node (ref "R99") (pin "2") (pinfunction "2_2") (pintype "passive"))
      (node (ref "T1") (pin "5") (pinfunction "5_5") (pintype "passive"))
      (node (ref "T1") (pin "8") (pinfunction "8_8") (pintype "passive"))
      (node (ref "U1") (pin "20") (pinfunction "GND_20") (pintype "passive"))
      (node (ref "U1") (pin "35") (pinfunction "GND_35") (pintype "passive"))
      (node (ref "U2") (pin "58") (pinfunction "AGND_58") (pintype "passive"))
      (node (ref "U2") (pin "8") (pinfunction "GND_8") (pintype "passive"))
      (node (ref "U3") (pin "8") (pinfunction "G_8") (pintype "passive"))
      (node (ref "U4") (pin "1") (pinfunction "VSS_1") (pintype "passive"))
      (node (ref "U4") (pin "14") (pinfunction "TH2_14") (pintype "passive"))
    )
    (net (code "72") (name "Net-(C2-Pad1)") (class "Default")
      (node (ref "C2") (pin "1") (pinfunction "1_1") (pintype "passive"))
      (node (ref "R1") (pin "2") (pinfunction "2_2") (pintype "passive"))
      (node (ref "R2") (pin "2") (pinfunction "2_2") (pintype "passive"))
      (node (ref "R3") (pin "2") (pinfunction "2_2") (pintype "passive"))
      (node (ref "R5") (pin "2") (pinfunction "2_2") (pintype "passive"))
    )
    (net (code "73") (name "Net-(C2-Pad2)") (class "Default")
      (node (ref "C2") (pin "2") (pinfunction "2_2") (pintype "passive"))
      (node (ref "D1") (pin "A") (pinfunction "A_A") (pintype "passive"))
      (node (ref "D3") (pin "A") (pinfunction "A_A") (pintype "passive"))
      (node (ref "T1") (pin "7") (pinfunction "7_7") (pintype "passive"))
    )
    (net (code "74") (name "Net-(C3-Pad1)") (class "Default")
      (node (ref "C3") (pin "1") (pinfunction "1_1") (pintype "passive"))
      (node (ref "D2") (pin "K") (pinfunction "K_K") (pintype "passive"))
      (node (ref "R4") (pin "2") (pinfunction "2_2") (pintype "passive"))
    )
    (net (code "75") (name "Net-(C15-Pad1)") (class "Default")
      (node (ref "C15") (pin "1") (pinfunction "1_1") (pintype "passive"))
      (node (ref "R14") (pin "1") (pinfunction "1_1") (pintype "passive"))
    )
    (net (code "76") (name "Net-(C16-Pad1)") (class "Default")
      (node (ref "C16") (pin "1") (pinfunction "1_1") (pintype "passive"))
      (node (ref "R19") (pin "2") (pinfunction "2_2") (pintype "passive"))
    )
    (net (code "77") (name "Net-(C16-Pad2)") (class "Default")
      (node (ref "C16") (pin "2") (pinfunction "2_2") (pintype "passive"))
      (node (ref "IC4") (pin "K") (pinfunction "K_K") (pintype "passive"))
      (node (ref "IC5") (pin "3") (pinfunction "3_3") (pintype "passive"))
      (node (ref "R12") (pin "1") (pinfunction "1_1") (pintype "passive"))
    )
    (net (code "78") (name "Net-(C17-Pad2)") (class "Default")
      (node (ref "C17") (pin "2") (pinfunction "2_2") (pintype "passive"))
      (node (ref "R31") (pin "1") (pinfunction "1_1") (pintype "passive"))
    )
    (net (code "79") (name "Net-(C21-Pad2)") (class "Default")
      (node (ref "C21") (pin "2") (pinfunction "2_2") (pintype "passive"))
      (node (ref "R30") (pin "1") (pinfunction "1_1") (pintype "passive"))
    )
    (net (code "80") (name "Net-(C52-Pad1)") (class "Default")
      (node (ref "C52") (pin "1") (pinfunction "1_1") (pintype "passive"))
      (node (ref "R76") (pin "1") (pinfunction "1_1") (pintype "passive"))
      (node (ref "R77") (pin "2") (pinfunction "2_2") (pintype "passive"))
    )
    (net (code "81") (name "Net-(C52-Pad2)") (class "Default")
      (node (ref "C52") (pin "2") (pinfunction "2_2") (pintype "passive"))
      (node (ref "R82") (pin "1") (pinfunction "1_1") (pintype "passive"))
      (node (ref "R83") (pin "2") (pinfunction "2_2") (pintype "passive"))
    )
    (net (code "82") (name "Net-(C58-Pad1)") (class "Default")
      (node (ref "C58") (pin "1") (pinfunction "1_1") (pintype "passive"))
      (node (ref "R97") (pin "2") (pinfunction "2_2") (pintype "passive"))
      (node (ref "R98") (pin "1") (pinfunction "1_1") (pintype "passive"))
    )
    (net (code "83") (name "Net-(C58-Pad2)") (class "Default")
      (node (ref "C58") (pin "2") (pinfunction "2_2") (pintype "passive"))
      (node (ref "R103") (pin "2") (pinfunction "2_2") (pintype "passive"))
      (node (ref "R104") (pin "1") (pinfunction "1_1") (pintype "passive"))
    )
    (net (code "84") (name "Net-(C61-Pad2)") (class "Default")
      (node (ref "C61") (pin "2") (pinfunction "2_2") (pintype "passive"))
      (node (ref "R102") (pin "2") (pinfunction "2_2") (pintype "passive"))
      (node (ref "R103") (pin "1") (pinfunction "1_1") (pintype "passive"))
      (node (ref "R113") (pin "2") (pinfunction "2_2") (pintype "passive"))
    )
    (net (code "85") (name "Net-(C70-Pad1)") (class "Default")
      (node (ref "C70") (pin "1") (pintype "passive"))
      (node (ref "IC8") (pin "K") (pinfunction "K_K") (pintype "passive"))
      (node (ref "IC9") (pin "C") (pinfunction "C_C") (pintype "passive"))
      (node (ref "R139") (pin "2") (pinfunction "2_2") (pintype "passive"))
    )
    (net (code "86") (name "Net-(C74-Pad1)") (class "Default")
      (node (ref "C74") (pin "1") (pintype "passive"))
      (node (ref "IC8") (pin "E") (pinfunction "E_E") (pintype "passive"))
      (node (ref "R138") (pin "1") (pinfunction "1_1") (pintype "passive"))
      (node (ref "R142") (pin "1") (pinfunction "1_1") (pintype "passive"))
    )
    (net (code "87") (name "Net-(C75-Pad2)") (class "Default")
      (node (ref "C75") (pin "2") (pintype "passive"))
      (node (ref "D15") (pin "A") (pinfunction "A_A") (pintype "passive"))
      (node (ref "IC9") (pin "E") (pinfunction "E_E") (pintype "passive"))
      (node (ref "R146") (pin "1") (pinfunction "1_1") (pintype "passive"))
      (node (ref "R151") (pin "1") (pinfunction "1_1") (pintype "passive"))
    )
    (net (code "88") (name "Net-(C77-Pad1)") (class "Default")
      (node (ref "C77") (pin "1") (pintype "passive"))
      (node (ref "IC9") (pin "A") (pinfunction "A_A") (pintype "passive"))
      (node (ref "R145") (pin "2") (pinfunction "2_2") (pintype "passive"))
      (node (ref "R149") (pin "1") (pinfunction "1_1") (pintype "passive"))
    )
    (net (code "89") (name "Net-(C77-Pad2)") (class "Default")
      (node (ref "C77") (pin "2") (pintype "passive"))
      (node (ref "IC9") (pin "K") (pinfunction "K_K") (pintype "passive"))
      (node (ref "Q6") (pin "C") (pinfunction "C_C") (pintype "passive"))
      (node (ref "R149") (pin "2") (pinfunction "2_2") (pintype "passive"))
    )
    (net (code "90") (name "Net-(CN2-Pad1)") (class "Default")
      (node (ref "CN2") (pin "1") (pinfunction "1_1") (pintype "passive"))
      (node (ref "FUSE1") (pin "1") (pinfunction "1_1") (pintype "passive"))
    )
    (net (code "91") (name "Net-(CN5-Pad2)") (class "Default")
      (node (ref "CN5") (pin "2") (pinfunction "2_2") (pintype "passive"))
      (node (ref "RY4") (pin "2") (pinfunction "2_2") (pintype "passive"))
    )
    (net (code "92") (name "Net-(CN8-Pad1)") (class "Default")
      (node (ref "CN8") (pin "1") (pinfunction "1_1") (pintype "passive"))
      (node (ref "RY5") (pin "2") (pinfunction "2_2") (pintype "passive"))
    )
    (net (code "93") (name "Net-(CN10-Pad1)") (class "Default")
      (node (ref "CN10") (pin "1") (pinfunction "1_1") (pintype "passive"))
      (node (ref "D10") (pin "KA") (pinfunction "KA_KA") (pintype "passive"))
      (node (ref "E14") (pin "1") (pintype "passive"))
      (node (ref "R94") (pin "1") (pinfunction "1_1") (pintype "passive"))
      (node (ref "R99") (pin "1") (pinfunction "1_1") (pintype "passive"))
    )
    (net (code "94") (name "Net-(CN10-Pad4)") (class "Default")
      (node (ref "CN10") (pin "4") (pinfunction "4_4") (pintype "passive"))
      (node (ref "D11") (pin "KA") (pinfunction "KA_KA") (pintype "passive"))
      (node (ref "E15") (pin "1") (pintype "passive"))
      (node (ref "R111") (pin "1") (pinfunction "1_1") (pintype "passive"))
      (node (ref "R119") (pin "1") (pinfunction "1_1") (pintype "passive"))
    )
    (net (code "95") (name "Net-(CN10-Pad6)") (class "Default")
      (node (ref "CN10") (pin "6") (pinfunction "6_6") (pintype "passive"))
      (node (ref "D12") (pin "KA") (pinfunction "KA_KA") (pintype "passive"))
      (node (ref "E16") (pin "1") (pinfunction "1_1") (pintype "passive"))
      (node (ref "R121") (pin "2") (pinfunction "2_2") (pintype "passive"))
      (node (ref "R122") (pin "2") (pinfunction "2_2") (pintype "passive"))
    )
    (net (code "96") (name "Net-(CN13-Pad3)") (class "Default")
      (node (ref "CN13") (pin "3") (pinfunction "3_3") (pintype "passive"))
      (node (ref "R134") (pin "1") (pinfunction "1_1") (pintype "passive"))
      (node (ref "R136") (pin "1") (pinfunction "1_1") (pintype "passive"))
    )
    (net (code "97") (name "Net-(CN13-Pad4)") (class "Default")
      (node (ref "CN13") (pin "4") (pinfunction "4_4") (pintype "passive"))
      (node (ref "R135") (pin "1") (pinfunction "1_1") (pintype "passive"))
      (node (ref "R137") (pin "1") (pinfunction "1_1") (pintype "passive"))
    )
    (net (code "98") (name "Net-(CN15-Pad1)") (class "Default")
      (node (ref "CN15") (pin "1") (pinfunction "1_1") (pintype "passive"))
      (node (ref "L4") (pin "1") (pinfunction "1_1") (pintype "passive"))
    )
    (net (code "99") (name "Net-(D2-PadA)") (class "Default")
      (node (ref "D2") (pin "A") (pinfunction "A_A") (pintype "passive"))
      (node (ref "IC3") (pin "7") (pinfunction "D/ST_7") (pintype "power_in"))
      (node (ref "IC3") (pin "8") (pinfunction "D/ST_8") (pintype "power_in"))
      (node (ref "T1") (pin "3") (pinfunction "3_3") (pintype "passive"))
    )
    (net (code "100") (name "Net-(D4-PadA)") (class "Default")
      (node (ref "D4") (pin "A") (pinfunction "A_A") (pintype "passive"))
      (node (ref "R6") (pin "1") (pinfunction "1_1") (pintype "passive"))
    )
    (net (code "101") (name "Net-(D6-PadA)") (class "Default")
      (node (ref "D6") (pin "A") (pinfunction "A_A") (pintype "passive"))
      (node (ref "R6") (pin "2") (pinfunction "2_2") (pintype "passive"))
      (node (ref "T1") (pin "6") (pinfunction "6_6") (pintype "passive"))
    )
    (net (code "102") (name "Net-(D16-PadA)") (class "Default")
      (node (ref "D16") (pin "A") (pinfunction "A_A") (pintype "passive"))
      (node (ref "R146") (pin "2") (pinfunction "2_2") (pintype "passive"))
      (node (ref "R151") (pin "2") (pinfunction "2_2") (pintype "passive"))
    )
    (net (code "103") (name "Net-(D16-PadK)") (class "Default")
      (node (ref "D16") (pin "K") (pinfunction "K_K") (pintype "passive"))
      (node (ref "L3") (pin "2") (pinfunction "2_2") (pintype "passive"))
    )
    (net (code "104") (name "Net-(IC2-(1)Vin)") (class "Default")
      (node (ref "C10") (pin "1") (pinfunction "1_1") (pintype "passive"))
      (node (ref "D6") (pin "K") (pinfunction "K_K") (pintype "passive"))
      (node (ref "D8") (pin "K") (pinfunction "K_K") (pintype "passive"))
      (node (ref "E5") (pin "1") (pinfunction "1_1") (pintype "passive"))
      (node (ref "IC2") (pin "1") (pinfunction "(1)Vin_1") (pintype "passive"))
    )
    (net (code "105") (name "Net-(IC3-FB{slash}OLP)") (class "Default")
      (node (ref "C13") (pin "1") (pinfunction "1_1") (pintype "passive"))
      (node (ref "IC3") (pin "4") (pinfunction "FB/OLP_4") (pintype "power_in"))
      (node (ref "IC4") (pin "C") (pinfunction "C_C") (pintype "passive"))
    )
    (net (code "106") (name "Net-(IC3-S{slash}OCP)") (class "Default")
      (node (ref "IC3") (pin "1") (pinfunction "S/OCP_1") (pintype "input"))
      (node (ref "R8") (pin "1") (pinfunction "1_1") (pintype "passive"))
    )
    (net (code "107") (name "Net-(IC3-Vcc)") (class "Default")
      (node (ref "C6") (pin "2") (pinfunction "2_2") (pintype "passive"))
      (node (ref "D4") (pin "K") (pinfunction "K_K") (pintype "passive"))
      (node (ref "E4") (pin "1") (pinfunction "1_1") (pintype "passive"))
      (node (ref "IC3") (pin "5") (pinfunction "Vcc_5") (pintype "bidirectional"))
    )
    (net (code "108") (name "Net-(IC4-PadA)") (class "Default")
      (node (ref "IC4") (pin "A") (pinfunction "A_A") (pintype "passive"))
      (node (ref "R12") (pin "2") (pinfunction "2_2") (pintype "passive"))
      (node (ref "R7") (pin "1") (pinfunction "1_1") (pintype "passive"))
    )
    (net (code "109") (name "Net-(IC5-Pad1)") (class "Default")
      (node (ref "IC5") (pin "1") (pinfunction "1_1") (pintype "passive"))
      (node (ref "R19") (pin "1") (pinfunction "1_1") (pintype "passive"))
      (node (ref "R20") (pin "1") (pinfunction "1_1") (pintype "passive"))
      (node (ref "R9") (pin "1") (pinfunction "1_1") (pintype "passive"))
    )
    (net (code "110") (name "Net-(J1-Pad3)") (class "Default")
      (node (ref "J1") (pin "3") (pinfunction "3_3") (pintype "passive"))
      (node (ref "R176") (pin "1") (pinfunction "1_1") (pintype "passive"))
    )
    (net (code "111") (name "Net-(J1-Pad4)") (class "Default")
      (node (ref "J1") (pin "4") (pinfunction "4_4") (pintype "passive"))
      (node (ref "R180") (pin "1") (pinfunction "1_1") (pintype "passive"))
    )
    (net (code "112") (name "Net-(L3-Pad1)") (class "Default")
      (node (ref "L3") (pin "1") (pinfunction "1_1") (pintype "passive"))
      (node (ref "L4") (pin "2") (pinfunction "2_2") (pintype "passive"))
    )
    (net (code "113") (name "Net-(LED2-2)") (class "Default")
      (node (ref "LED2") (pin "K") (pinfunction "2_K") (pintype "passive"))
      (node (ref "R127") (pin "2") (pinfunction "2_2") (pintype "passive"))
    )
    (net (code "114") (name "Net-(LED3-2)") (class "Default")
      (node (ref "LED3") (pin "K") (pinfunction "2_K") (pintype "passive"))
      (node (ref "R125") (pin "2") (pinfunction "2_2") (pintype "passive"))
    )
    (net (code "115") (name "Net-(Q6-PadB)") (class "Default")
      (node (ref "Q6") (pin "B") (pinfunction "B_B") (pintype "passive"))
      (node (ref "R153") (pin "2") (pinfunction "2_2") (pintype "passive"))
      (node (ref "R160") (pin "1") (pinfunction "1_1") (pintype "passive"))
    )
    (net (code "116") (name "Net-(R10-Pad2)") (class "Default")
      (node (ref "R10") (pin "2") (pinfunction "2_2") (pintype "passive"))
      (node (ref "R18") (pin "1") (pinfunction "1_1") (pintype "passive"))
    )
    (net (code "117") (name "Net-(R11-Pad2)") (class "Default")
      (node (ref "R11") (pin "2") (pinfunction "2_2") (pintype "passive"))
      (node (ref "R17") (pin "1") (pinfunction "1_1") (pintype "passive"))
    )
    (net (code "118") (name "Net-(R13-Pad1)") (class "Default")
      (node (ref "R13") (pin "1") (pinfunction "1_1") (pintype "passive"))
      (node (ref "R168") (pin "1") (pinfunction "1_1") (pintype "passive"))
      (node (ref "R174") (pin "2") (pinfunction "2_2") (pintype "passive"))
    )
    (net (code "119") (name "Net-(R13-Pad2)") (class "Default")
      (node (ref "R13") (pin "2") (pinfunction "2_2") (pintype "passive"))
      (node (ref "R169") (pin "1") (pinfunction "1_1") (pintype "passive"))
    )
    (net (code "120") (name "Net-(R17-Pad2)") (class "Default")
      (node (ref "R17") (pin "2") (pinfunction "2_2") (pintype "passive"))
      (node (ref "R21") (pin "1") (pinfunction "1_1") (pintype "passive"))
    )
    (net (code "121") (name "Net-(R18-Pad2)") (class "Default")
      (node (ref "R18") (pin "2") (pinfunction "2_2") (pintype "passive"))
      (node (ref "R22") (pin "1") (pinfunction "1_1") (pintype "passive"))
    )
    (net (code "122") (name "Net-(R35-Pad1)") (class "Default")
      (node (ref "R35") (pin "1") (pinfunction "1_1") (pintype "passive"))
      (node (ref "R59") (pin "2") (pinfunction "2_2") (pintype "passive"))
    )
    (net (code "123") (name "Net-(R36-Pad2)") (class "Default")
      (node (ref "R36") (pin "2") (pinfunction "2_2") (pintype "passive"))
      (node (ref "R45") (pin "1") (pinfunction "1_1") (pintype "passive"))
    )
    (net (code "124") (name "Net-(R41-Pad1)") (class "Default")
      (node (ref "R41") (pin "1") (pinfunction "1_1") (pintype "passive"))
      (node (ref "R42") (pin "2") (pinfunction "2_2") (pintype "passive"))
    )
    (net (code "125") (name "Net-(R45-Pad2)") (class "Default")
      (node (ref "R45") (pin "2") (pinfunction "2_2") (pintype "passive"))
      (node (ref "R48") (pin "2") (pinfunction "2_2") (pintype "passive"))
      (node (ref "R75") (pin "1") (pinfunction "1_1") (pintype "passive"))
    )
    (net (code "126") (name "Net-(R57-Pad2)") (class "Default")
      (node (ref "R57") (pin "2") (pinfunction "2_2") (pintype "passive"))
      (node (ref "R59") (pin "1") (pinfunction "1_1") (pintype "passive"))
      (node (ref "R62") (pin "2") (pinfunction "2_2") (pintype "passive"))
    )
    (net (code "127") (name "Net-(R105-Pad2)") (class "Default")
      (node (ref "R105") (pin "2") (pinfunction "2_2") (pintype "passive"))
      (node (ref "R106") (pin "1") (pinfunction "1_1") (pintype "passive"))
    )
    (net (code "128") (name "Net-(R109-Pad2)") (class "Default")
      (node (ref "R109") (pin "2") (pinfunction "2_2") (pintype "passive"))
      (node (ref "R112") (pin "1") (pinfunction "1_1") (pintype "passive"))
      (node (ref "R118") (pin "2") (pinfunction "2_2") (pintype "passive"))
    )
    (net (code "129") (name "Net-(R114-Pad1)") (class "Default")
      (node (ref "R114") (pin "1") (pinfunction "1_1") (pintype "passive"))
      (node (ref "R117") (pin "1") (pinfunction "1_1") (pintype "passive"))
    )
    (net (code "130") (name "Net-(R116-Pad2)") (class "Default")
      (node (ref "R116") (pin "2") (pinfunction "2_2") (pintype "passive"))
      (node (ref "RA7") (pin "2") (pinfunction "2_2") (pintype "passive"))
      (node (ref "RB0") (pin "1") (pinfunction "1_1") (pintype "passive"))
    )
    (net (code "131") (name "Net-(U1-FLT{slash}EN)") (class "Default")
      (node (ref "R46") (pin "2") (pinfunction "2_2") (pintype "passive"))
      (node (ref "R50") (pin "2") (pinfunction "2_2") (pintype "passive"))
      (node (ref "R51") (pin "2") (pinfunction "2_2") (pintype "passive"))
      (node (ref "U1") (pin "31") (pinfunction "FLT/EN_31") (pintype "passive"))
    )
    (net (code "132") (name "Net-(U1-HIN1)") (class "Default")
      (node (ref "C47") (pin "1") (pinfunction "1_1") (pintype "passive"))
      (node (ref "R53") (pin "2") (pinfunction "2_2") (pintype "passive"))
      (node (ref "U1") (pin "29") (pinfunction "HIN1_29") (pintype "passive"))
    )
    (net (code "133") (name "Net-(U1-HIN2)") (class "Default")
      (node (ref "C48") (pin "1") (pinfunction "1_1") (pintype "passive"))
      (node (ref "R54") (pin "2") (pinfunction "2_2") (pintype "passive"))
      (node (ref "U1") (pin "28") (pinfunction "HIN2_28") (pintype "passive"))
    )
    (net (code "134") (name "Net-(U1-HIN3)") (class "Default")
      (node (ref "C49") (pin "1") (pinfunction "1_1") (pintype "passive"))
      (node (ref "R55") (pin "2") (pinfunction "2_2") (pintype "passive"))
      (node (ref "U1") (pin "27") (pinfunction "HIN3_27") (pintype "passive"))
    )
    (net (code "135") (name "Net-(U1-ITRIP)") (class "Default")
      (node (ref "C51") (pin "1") (pinfunction "1_1") (pintype "passive"))
      (node (ref "R75") (pin "2") (pinfunction "2_2") (pintype "passive"))
      (node (ref "U1") (pin "33") (pinfunction "ITRIP_33") (pintype "passive"))
    )
    (net (code "136") (name "Net-(U1-LIN1)") (class "Default")
      (node (ref "C50") (pin "1") (pinfunction "1_1") (pintype "passive"))
      (node (ref "R56") (pin "2") (pinfunction "2_2") (pintype "passive"))
      (node (ref "U1") (pin "26") (pinfunction "LIN1_26") (pintype "passive"))
    )
    (net (code "137") (name "Net-(U1-LIN2)") (class "Default")
      (node (ref "C45") (pin "1") (pinfunction "1_1") (pintype "passive"))
      (node (ref "R58") (pin "2") (pinfunction "2_2") (pintype "passive"))
      (node (ref "U1") (pin "25") (pinfunction "LIN2_25") (pintype "passive"))
    )
    (net (code "138") (name "Net-(U1-LIN3)") (class "Default")
      (node (ref "C46") (pin "1") (pinfunction "1_1") (pintype "passive"))
      (node (ref "R61") (pin "2") (pinfunction "2_2") (pintype "passive"))
      (node (ref "U1") (pin "24") (pinfunction "LIN3_24") (pintype "passive"))
    )
    (net (code "139") (name "Net-(U1-PFC)") (class "Default")
      (node (ref "CN6") (pin "1") (pinfunction "1_1") (pintype "passive"))
      (node (ref "L2") (pin "1") (pinfunction "1_1") (pintype "passive"))
      (node (ref "U1") (pin "1") (pinfunction "PFC_1") (pintype "passive"))
    )
    (net (code "140") (name "Net-(U1-PFCIN)") (class "Default")
      (node (ref "C44") (pin "1") (pinfunction "1_1") (pintype "passive"))
      (node (ref "R52") (pin "2") (pinfunction "2_2") (pintype "passive"))
      (node (ref "U1") (pin "30") (pinfunction "PFCIN_30") (pintype "passive"))
    )
    (net (code "141") (name "Net-(U1-PFCTRIP)") (class "Default")
      (node (ref "C56") (pin "2") (pinfunction "2_2") (pintype "passive"))
      (node (ref "R95") (pin "1") (pinfunction "1_1") (pintype "passive"))
      (node (ref "U1") (pin "32") (pinfunction "PFCTRIP_32") (pintype "passive"))
    )
    (net (code "142") (name "Net-(U1-VBU)") (class "Default")
      (node (ref "C39") (pin "1") (pinfunction "1_1") (pintype "passive"))
      (node (ref "E11") (pin "1") (pinfunction "1_1") (pintype "passive"))
      (node (ref "U1") (pin "12") (pinfunction "VBU_12") (pintype "passive"))
    )
    (net (code "143") (name "Net-(U1-VBV)") (class "Default")
      (node (ref "C37") (pin "1") (pinfunction "1_1") (pintype "passive"))
      (node (ref "E10") (pin "1") (pinfunction "1_1") (pintype "passive"))
      (node (ref "U1") (pin "8") (pinfunction "VBV_8") (pintype "passive"))
    )
    (net (code "144") (name "Net-(U1-VBW)") (class "Default")
      (node (ref "C35") (pin "1") (pinfunction "1_1") (pintype "passive"))
      (node (ref "E9") (pin "1") (pinfunction "1_1") (pintype "passive"))
      (node (ref "U1") (pin "4") (pinfunction "VBW_4") (pintype "passive"))
    )
    (net (code "145") (name "Net-(U2-ADC1_AN2{slash}PD9)") (class "Default")
      (node (ref "C38") (pin "2") (pinfunction "2_2") (pintype "passive"))
      (node (ref "R60") (pin "1") (pinfunction "1_1") (pintype "passive"))
      (node (ref "U2") (pin "71") (pinfunction "ADC1_AN2/PD9_71") (pintype "passive"))
    )
    (net (code "146") (name "Net-(U2-ADC2_AN2{slash}PD0)") (class "Default")
      (node (ref "C40") (pin "2") (pinfunction "2_2") (pintype "passive"))
      (node (ref "R66") (pin "1") (pinfunction "1_1") (pintype "passive"))
      (node (ref "U2") (pin "62") (pinfunction "ADC2_AN2/PD0_62") (pintype "passive"))
    )
    (net (code "147") (name "Net-(U2-ADC12_AN0{slash}PD7)") (class "Default")
      (node (ref "C55") (pin "1") (pinfunction "1_1") (pintype "passive"))
      (node (ref "R86") (pin "2") (pinfunction "2_2") (pintype "passive"))
      (node (ref "U2") (pin "69") (pinfunction "ADC12_AN0/PD7_69") (pintype "passive"))
    )
    (net (code "148") (name "Net-(U2-BOOT{slash}PE8)") (class "Default")
      (node (ref "R123") (pin "1") (pinfunction "1_1") (pintype "passive"))
      (node (ref "U2") (pin "11") (pinfunction "BOOT/PE8_11") (pintype "passive"))
    )
    (net (code "149") (name "Net-(U2-CP1N{slash}PE5)") (class "Default")
      (node (ref "R32") (pin "1") (pinfunction "1_1") (pintype "passive"))
      (node (ref "U2") (pin "3") (pinfunction "CP1N/PE5_3") (pintype "passive"))
    )
    (net (code "150") (name "Net-(U2-CP1OUT{slash}PE6)") (class "Default")
      (node (ref "R34") (pin "2") (pinfunction "2_2") (pintype "passive"))
      (node (ref "U2") (pin "4") (pinfunction "CP1OUT/PE6_4") (pintype "passive"))
    )
    (net (code "151") (name "Net-(U2-CP2OUT{slash}PE3)") (class "Default")
      (node (ref "U2") (pin "1") (pinfunction "CP2OUT/PE3_1") (pintype "passive"))
      (node (ref "U2") (pin "5") (pinfunction "PE7_5") (pintype "passive"))
    )
    (net (code "152") (name "Net-(U2-JTRST{slash}PA2)") (class "Default")
      (node (ref "R39") (pin "2") (pinfunction "2_2") (pintype "passive"))
      (node (ref "U2") (pin "12") (pinfunction "JTRST/PA2_12") (pintype "passive"))
    )
    (net (code "153") (name "Net-(U2-PA10{slash}GTIOC0A{slash}SS1)") (class "Default")
      (node (ref "R31") (pin "2") (pinfunction "2_2") (pintype "passive"))
      (node (ref "U2") (pin "21") (pinfunction "PA10/GTIOC0A/SS1_21") (pintype "passive"))
    )
    (net (code "154") (name "Net-(U2-PA11{slash}GTIOC1A{slash}RXD1)") (class "Default")
      (node (ref "R30") (pin "2") (pinfunction "2_2") (pintype "passive"))
      (node (ref "U2") (pin "22") (pinfunction "PA11/GTIOC1A/RXD1_22") (pintype "passive"))
    )
    (net (code "155") (name "Net-(U2-PA12{slash}GTIOC2A{slash}TXD1)") (class "Default")
      (node (ref "R28") (pin "2") (pinfunction "2_2") (pintype "passive"))
      (node (ref "U2") (pin "23") (pinfunction "PA12/GTIOC2A/TXD1_23") (pintype "passive"))
    )
    (net (code "156") (name "Net-(U2-PA13{slash}GTIOC0B{slash}SCK1)") (class "Default")
      (node (ref "R26") (pin "2") (pinfunction "2_2") (pintype "passive"))
      (node (ref "U2") (pin "24") (pinfunction "PA13/GTIOC0B/SCK1_24") (pintype "passive"))
    )
    (net (code "157") (name "Net-(U2-PA14{slash}GTIOC1B{slash}MOSI1)") (class "Default")
      (node (ref "R25") (pin "2") (pinfunction "2_2") (pintype "passive"))
      (node (ref "U2") (pin "25") (pinfunction "PA14/GTIOC1B/MOSI1_25") (pintype "passive"))
    )
    (net (code "158") (name "Net-(U2-PB2{slash}GTPOE)") (class "Default")
      (node (ref "R23") (pin "2") (pinfunction "2_2") (pintype "passive"))
      (node (ref "U2") (pin "29") (pinfunction "PB2/GTPOE_29") (pintype "passive"))
    )
    (net (code "159") (name "Net-(U2-PB3{slash}MOSI2{slash}GTETRG)") (class "Default")
      (node (ref "R79") (pin "2") (pinfunction "2_2") (pintype "passive"))
      (node (ref "U2") (pin "30") (pinfunction "PB3/MOSI2/GTETRG_30") (pintype "passive"))
    )
    (net (code "160") (name "Net-(U2-PB4{slash}MISO2{slash}GTIOC3A{slash}MCM1_SC0)") (class "Default")
      (node (ref "R78") (pin "2") (pinfunction "2_2") (pintype "passive"))
      (node (ref "U2") (pin "31") (pinfunction "PB4/MISO2/GTIOC3A/MCM1_SC0_31") (pintype "passive"))
    )
    (net (code "161") (name "Net-(U2-PB5{slash}SCK2{slash}GTIOC3A1{slash}MCM1_SC1)") (class "Default")
      (node (ref "R74") (pin "2") (pinfunction "2_2") (pintype "passive"))
      (node (ref "U2") (pin "32") (pinfunction "PB5/SCK2/GTIOC3A1/MCM1_SC1_32") (pintype "passive"))
    )
    (net (code "162") (name "Net-(U2-PB6{slash}SS2{slash}GTIOC3A2{slash}MCM1_SC2)") (class "Default")
      (node (ref "R33") (pin "1") (pinfunction "1_1") (pintype "passive"))
      (node (ref "U2") (pin "33") (pinfunction "PB6/SS2/GTIOC3A2/MCM1_SC2_33") (pintype "passive"))
    )
    (net (code "163") (name "Net-(U2-PE4)") (class "Default")
      (node (ref "R24") (pin "1") (pinfunction "1_1") (pintype "passive"))
      (node (ref "U2") (pin "2") (pinfunction "PE4_2") (pintype "passive"))
    )
    (net (code "164") (name "Net-(U2-PE9)") (class "Default")
      (node (ref "R127") (pin "1") (pinfunction "1_1") (pintype "passive"))
      (node (ref "U2") (pin "19") (pinfunction "PE9_19") (pintype "passive"))
    )
    (net (code "165") (name "Net-(U2-QEA{slash}GTIOC3B{slash}PA7)") (class "Default")
      (node (ref "R125") (pin "1") (pinfunction "1_1") (pintype "passive"))
      (node (ref "U2") (pin "17") (pinfunction "QEA/GTIOC3B/PA7_17") (pintype "passive"))
    )
    (net (code "166") (name "Net-(U2-RXD3{slash}JTDI{slash}PA3)") (class "Default")
      (node (ref "R40") (pin "2") (pinfunction "2_2") (pintype "passive"))
      (node (ref "U2") (pin "13") (pinfunction "RXD3/JTDI/PA3_13") (pintype "passive"))
    )
    (net (code "167") (name "Net-(U2-T7{slash}XTAL2{slash}PA0)") (class "Default")
      (node (ref "R37") (pin "1") (pinfunction "1_1") (pintype "passive"))
      (node (ref "U2") (pin "7") (pinfunction "T7/XTAL2/PA0_7") (pintype "passive"))
    )
    (net (code "168") (name "Net-(U2-T8{slash}XTAL1{slash}PA1)") (class "Default")
      (node (ref "R38") (pin "2") (pinfunction "2_2") (pintype "passive"))
      (node (ref "U2") (pin "9") (pinfunction "T8/XTAL1/PA1_9") (pintype "passive"))
    )
    (net (code "169") (name "Net-(U2-TXD3{slash}SWO{slash}JTDO{slash}PA6)") (class "Default")
      (node (ref "R124") (pin "2") (pinfunction "2_2") (pintype "passive"))
      (node (ref "U2") (pin "16") (pinfunction "TXD3/SWO/JTDO/PA6_16") (pintype "passive"))
    )
    (net (code "170") (name "Net-(U3-2C)") (class "Default")
      (node (ref "CN9") (pin "4") (pinfunction "4_4") (pintype "passive"))
      (node (ref "U3") (pin "15") (pinfunction "2C_15") (pintype "open_collector"))
    )
    (net (code "171") (name "Net-(U3-3C)") (class "Default")
      (node (ref "CN9") (pin "3") (pinfunction "3_3") (pintype "passive"))
      (node (ref "U3") (pin "14") (pinfunction "3C_14") (pintype "open_collector"))
    )
    (net (code "172") (name "Net-(U3-4C)") (class "Default")
      (node (ref "CN9") (pin "2") (pinfunction "2_2") (pintype "passive"))
      (node (ref "U3") (pin "13") (pinfunction "4C_13") (pintype "open_collector"))
    )
    (net (code "173") (name "Net-(U3-5C)") (class "Default")
      (node (ref "CN9") (pin "1") (pinfunction "1_1") (pintype "passive"))
      (node (ref "U3") (pin "12") (pinfunction "5C_12") (pintype "open_collector"))
    )
    (net (code "174") (name "Net-(U3-7C)") (class "Default")
      (node (ref "RY4") (pin "4") (pinfunction "4_4") (pintype "passive"))
      (node (ref "U3") (pin "10") (pinfunction "7C_10") (pintype "open_collector"))
    )
    (net (code "175") (name "Net-(U4-ENABLE)") (class "Default")
      (node (ref "R161") (pin "2") (pinfunction "2_2") (pintype "passive"))
      (node (ref "R162") (pin "2") (pinfunction "2_2") (pintype "passive"))
      (node (ref "U4") (pin "11") (pinfunction "ENABLE_11") (pintype "passive"))
      (node (ref "U4") (pin "9") (pinfunction "FAULT_9") (pintype "passive"))
    )
    (net (code "176") (name "Net-(U4-HIN1)") (class "Default")
      (node (ref "C80") (pin "1") (pinfunction "1_1") (pintype "passive"))
      (node (ref "R143") (pin "2") (pinfunction "2_2") (pintype "passive"))
      (node (ref "U4") (pin "3") (pinfunction "HIN1_3") (pintype "passive"))
    )
    (net (code "177") (name "Net-(U4-HIN2)") (class "Default")
      (node (ref "C81") (pin "1") (pinfunction "1_1") (pintype "passive"))
      (node (ref "R144") (pin "2") (pinfunction "2_2") (pintype "passive"))
      (node (ref "U4") (pin "4") (pinfunction "HIN2_4") (pintype "passive"))
    )
    (net (code "178") (name "Net-(U4-HIN3)") (class "Default")
      (node (ref "C84") (pin "1") (pinfunction "1_1") (pintype "passive"))
      (node (ref "R147") (pin "2") (pinfunction "2_2") (pintype "passive"))
      (node (ref "U4") (pin "5") (pinfunction "HIN3_5") (pintype "passive"))
    )
    (net (code "179") (name "Net-(U4-ITRIP)") (class "Default")
      (node (ref "C91") (pin "1") (pinfunction "1_1") (pintype "passive"))
      (node (ref "R168") (pin "2") (pinfunction "2_2") (pintype "passive"))
      (node (ref "U4") (pin "10") (pinfunction "ITRIP_10") (pintype "passive"))
    )
    (net (code "180") (name "Net-(U4-LIN1)") (class "Default")
      (node (ref "C82") (pin "1") (pinfunction "1_1") (pintype "passive"))
      (node (ref "R148") (pin "2") (pinfunction "2_2") (pintype "passive"))
      (node (ref "U4") (pin "6") (pinfunction "LIN1_6") (pintype "passive"))
    )
    (net (code "181") (name "Net-(U4-LIN2)") (class "Default")
      (node (ref "C83") (pin "1") (pinfunction "1_1") (pintype "passive"))
      (node (ref "R150") (pin "2") (pinfunction "2_2") (pintype "passive"))
      (node (ref "U4") (pin "7") (pinfunction "LIN2_7") (pintype "passive"))
    )
    (net (code "182") (name "Net-(U4-LIN3)") (class "Default")
      (node (ref "C79") (pin "1") (pinfunction "1_1") (pintype "passive"))
      (node (ref "R152") (pin "2") (pinfunction "2_2") (pintype "passive"))
      (node (ref "U4") (pin "8") (pinfunction "LIN3_8") (pintype "passive"))
    )
    (net (code "183") (name "Net-(U4-RCIN)") (class "Default")
      (node (ref "C86") (pin "2") (pinfunction "2_2") (pintype "passive"))
      (node (ref "U4") (pin "12") (pinfunction "RCIN_12") (pintype "passive"))
    )
    (net (code "184") (name "Net-(U4-TH1)") (class "Default")
      (node (ref "R140") (pin "2") (pinfunction "2_2") (pintype "passive"))
      (node (ref "R141") (pin "2") (pinfunction "2_2") (pintype "passive"))
      (node (ref "U4") (pin "13") (pinfunction "TH1_13") (pintype "passive"))
    )
    (net (code "185") (name "Net-(U4-U-)") (class "Default")
      (node (ref "R165") (pin "1") (pinfunction "1_1") (pintype "passive"))
      (node (ref "R169") (pin "2") (pinfunction "2_2") (pintype "passive"))
      (node (ref "R170") (pin "1") (pinfunction "1_1") (pintype "passive"))
      (node (ref "U4") (pin "17") (pinfunction "U-_17") (pintype "passive"))
      (node (ref "U4") (pin "18") (pinfunction "V-_18") (pintype "passive"))
      (node (ref "U4") (pin "19") (pinfunction "W-_19") (pintype "passive"))
    )
    (net (code "186") (name "Net-(U4-VB1)") (class "Default")
      (node (ref "C76") (pin "1") (pinfunction "1_1") (pintype "passive"))
      (node (ref "E17") (pin "1") (pinfunction "1_1") (pintype "passive"))
      (node (ref "U4") (pin "34") (pinfunction "VB1_34") (pintype "passive"))
    )
    (net (code "187") (name "Net-(U4-VB2)") (class "Default")
      (node (ref "C78") (pin "1") (pinfunction "1_1") (pintype "passive"))
      (node (ref "E18") (pin "1") (pinfunction "1_1") (pintype "passive"))
      (node (ref "U4") (pin "28") (pinfunction "VB2_28") (pintype "passive"))
    )
    (net (code "188") (name "Net-(U4-VB3)") (class "Default")
      (node (ref "C85") (pin "1") (pinfunction "1_1") (pintype "passive"))
      (node (ref "E19") (pin "1") (pinfunction "1_1") (pintype "passive"))
      (node (ref "U4") (pin "22") (pinfunction "VB3_22") (pintype "passive"))
    )
    (net (code "189") (name "P+") (class "Default")
      (node (ref "C3") (pin "2") (pinfunction "2_2") (pintype "passive"))
      (node (ref "C42") (pin "2") (pinfunction "2_2") (pintype "passive"))
      (node (ref "C72") (pin "1") (pinfunction "1_1") (pintype "passive"))
      (node (ref "E12") (pin "1") (pinfunction "1_1") (pintype "passive"))
      (node (ref "R35") (pin "2") (pinfunction "2_2") (pintype "passive"))
      (node (ref "R4") (pin "1") (pinfunction "1_1") (pintype "passive"))
      (node (ref "R41") (pin "2") (pinfunction "2_2") (pintype "passive"))
      (node (ref "T1") (pin "1") (pinfunction "1_1") (pintype "passive"))
      (node (ref "U1") (pin "16") (pinfunction "VCC1_16") (pintype "passive"))
      (node (ref "U1") (pin "17") (pinfunction "VCC2_17") (pintype "passive"))
      (node (ref "U4") (pin "38") (pinfunction "VCC1_38") (pintype "passive"))
    )
    (net (code "190") (name "VCC") (class "Default")
      (node (ref "C1") (pin "2") (pinfunction "2_2") (pintype "passive"))
      (node (ref "C27") (pin "2") (pinfunction "2_2") (pintype "passive"))
      (node (ref "C28") (pin "2") (pinfunction "2_2") (pintype "passive"))
      (node (ref "C34") (pin "1") (pinfunction "1_1") (pintype "passive"))
      (node (ref "C4") (pin "1") (pinfunction "1_1") (pintype "passive"))
      (node (ref "C65") (pin "2") (pinfunction "2_2") (pintype "passive"))
      (node (ref "C69") (pin "2") (pinfunction "2_2") (pintype "passive"))
      (node (ref "C92") (pin "2") (pinfunction "2_2") (pintype "passive"))
      (node (ref "CN10") (pin "2") (pinfunction "2_2") (pintype "passive"))
      (node (ref "CN10") (pin "5") (pinfunction "5_5") (pintype "passive"))
      (node (ref "CN10") (pin "7") (pinfunction "7_7") (pintype "passive"))
      (node (ref "CN13") (pin "1") (pinfunction "1_1") (pintype "passive"))
      (node (ref "D10") (pin "K") (pinfunction "K_K") (pintype "passive"))
      (node (ref "D11") (pin "K") (pinfunction "K_K") (pintype "passive"))
      (node (ref "D12") (pin "K") (pinfunction "K_K") (pintype "passive"))
      (node (ref "D7") (pin "A") (pinfunction "A_A") (pintype "passive"))
      (node (ref "D9") (pin "K") (pinfunction "K_K") (pintype "passive"))
      (node (ref "E1") (pin "1") (pinfunction "1_1") (pintype "passive"))
      (node (ref "IC1") (pin "3") (pinfunction "(3)Vout_3") (pintype "passive"))
      (node (ref "IC8") (pin "C") (pinfunction "C_C") (pintype "passive"))
      (node (ref "J1") (pin "1") (pinfunction "1_1") (pintype "passive"))
      (node (ref "LED2") (pin "A") (pinfunction "1_A") (pintype "passive"))
      (node (ref "LED3") (pin "A") (pinfunction "1_A") (pintype "passive"))
      (node (ref "R112") (pin "2") (pinfunction "2_2") (pintype "passive"))
      (node (ref "R126") (pin "1") (pinfunction "1_1") (pintype "passive"))
      (node (ref "R134") (pin "2") (pinfunction "2_2") (pintype "passive"))
      (node (ref "R135") (pin "2") (pinfunction "2_2") (pintype "passive"))
      (node (ref "R140") (pin "1") (pinfunction "1_1") (pintype "passive"))
      (node (ref "R145") (pin "1") (pinfunction "1_1") (pintype "passive"))
      (node (ref "R16") (pin "2") (pinfunction "2_2") (pintype "passive"))
      (node (ref "R161") (pin "1") (pinfunction "1_1") (pintype "passive"))
      (node (ref "R171") (pin "2") (pinfunction "2_2") (pintype "passive"))
      (node (ref "R36") (pin "1") (pinfunction "1_1") (pintype "passive"))
      (node (ref "R50") (pin "1") (pinfunction "1_1") (pintype "passive"))
      (node (ref "R63") (pin "2") (pinfunction "2_2") (pintype "passive"))
      (node (ref "R89") (pin "2") (pinfunction "2_2") (pintype "passive"))
      (node (ref "RB0") (pin "2") (pinfunction "2_2") (pintype "passive"))
      (node (ref "U2") (pin "10") (pinfunction "VDD_10") (pintype "passive"))
      (node (ref "U2") (pin "56") (pinfunction "AVDD_56") (pintype "passive"))
    )
    (net (code "191") (name "unconnected-(CN10-Pad3)") (class "Default")
      (node (ref "CN10") (pin "3") (pinfunction "3_3") (pintype "passive+no_connect"))
    )
    (net (code "192") (name "unconnected-(T1-Pad2)") (class "Default")
      (node (ref "T1") (pin "2") (pinfunction "2_2") (pintype "passive"))
    )
  )
)
